# DC309A_RXIN.net
KiCad netlist of a schematic drawn in Altium Designer
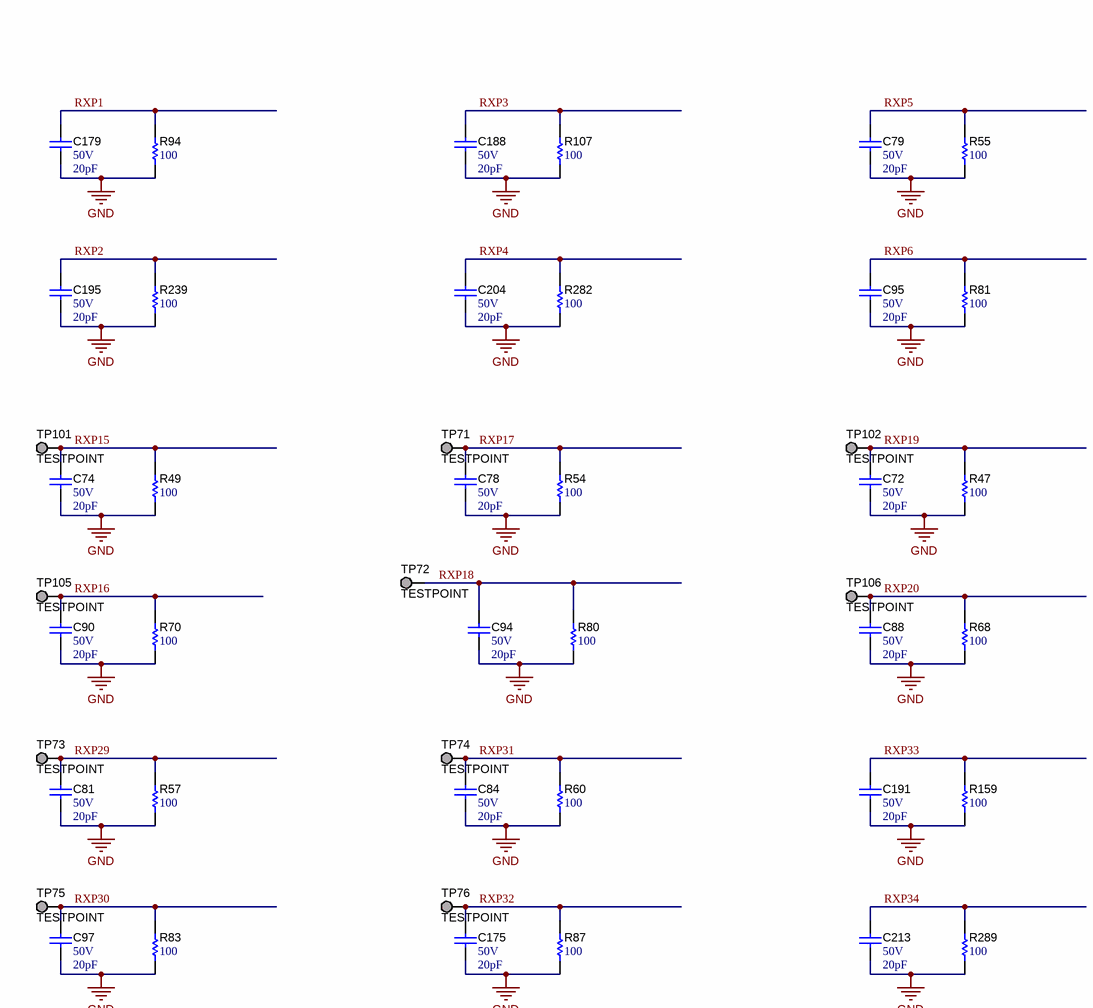
[diagram p0: DC309A_RXIN.SchDoc, top left]
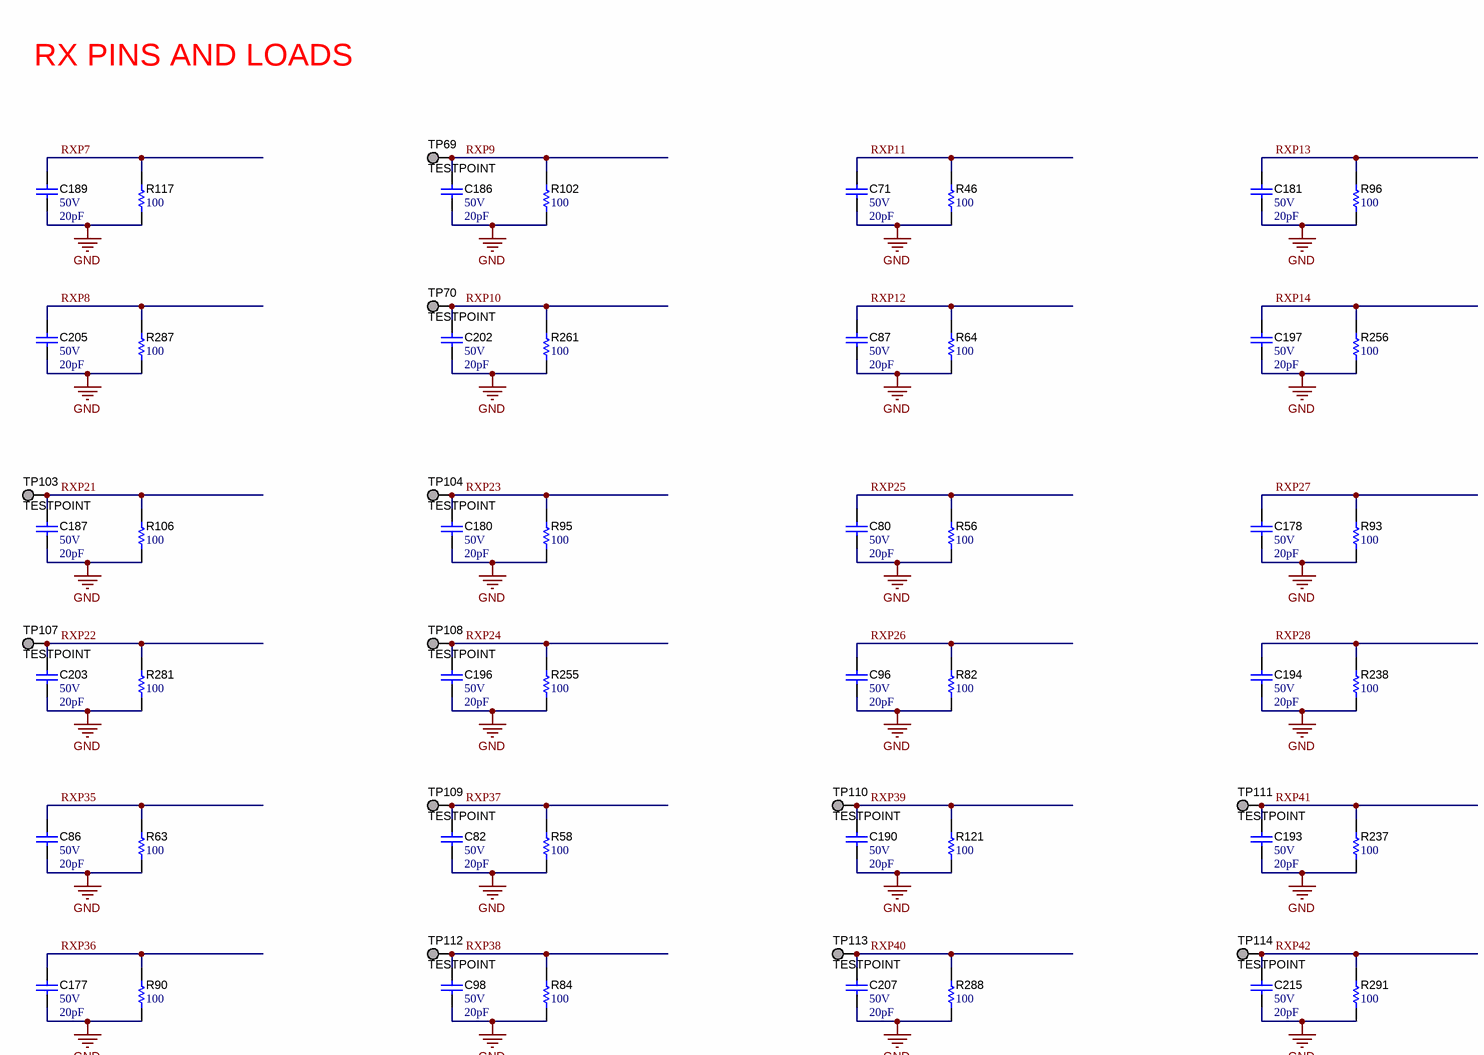
[diagram p1: DC309A_RXIN.SchDoc, top right]
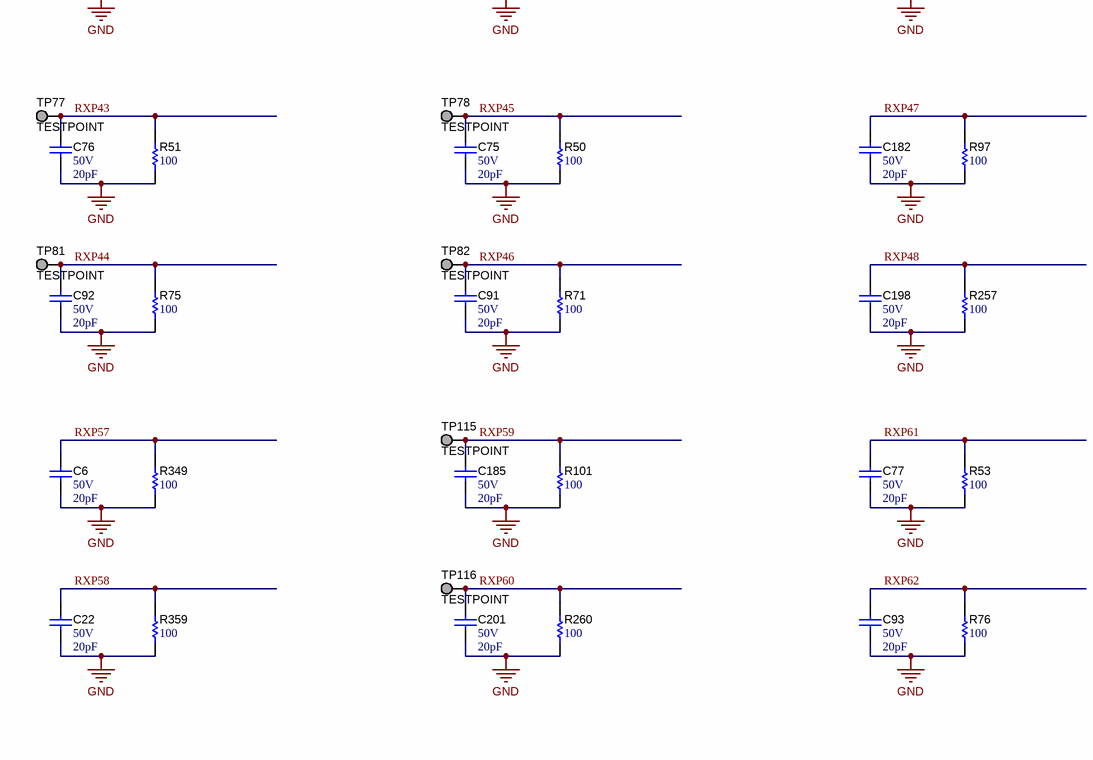
[diagram p2: DC309A_RXIN.SchDoc, bottom left]
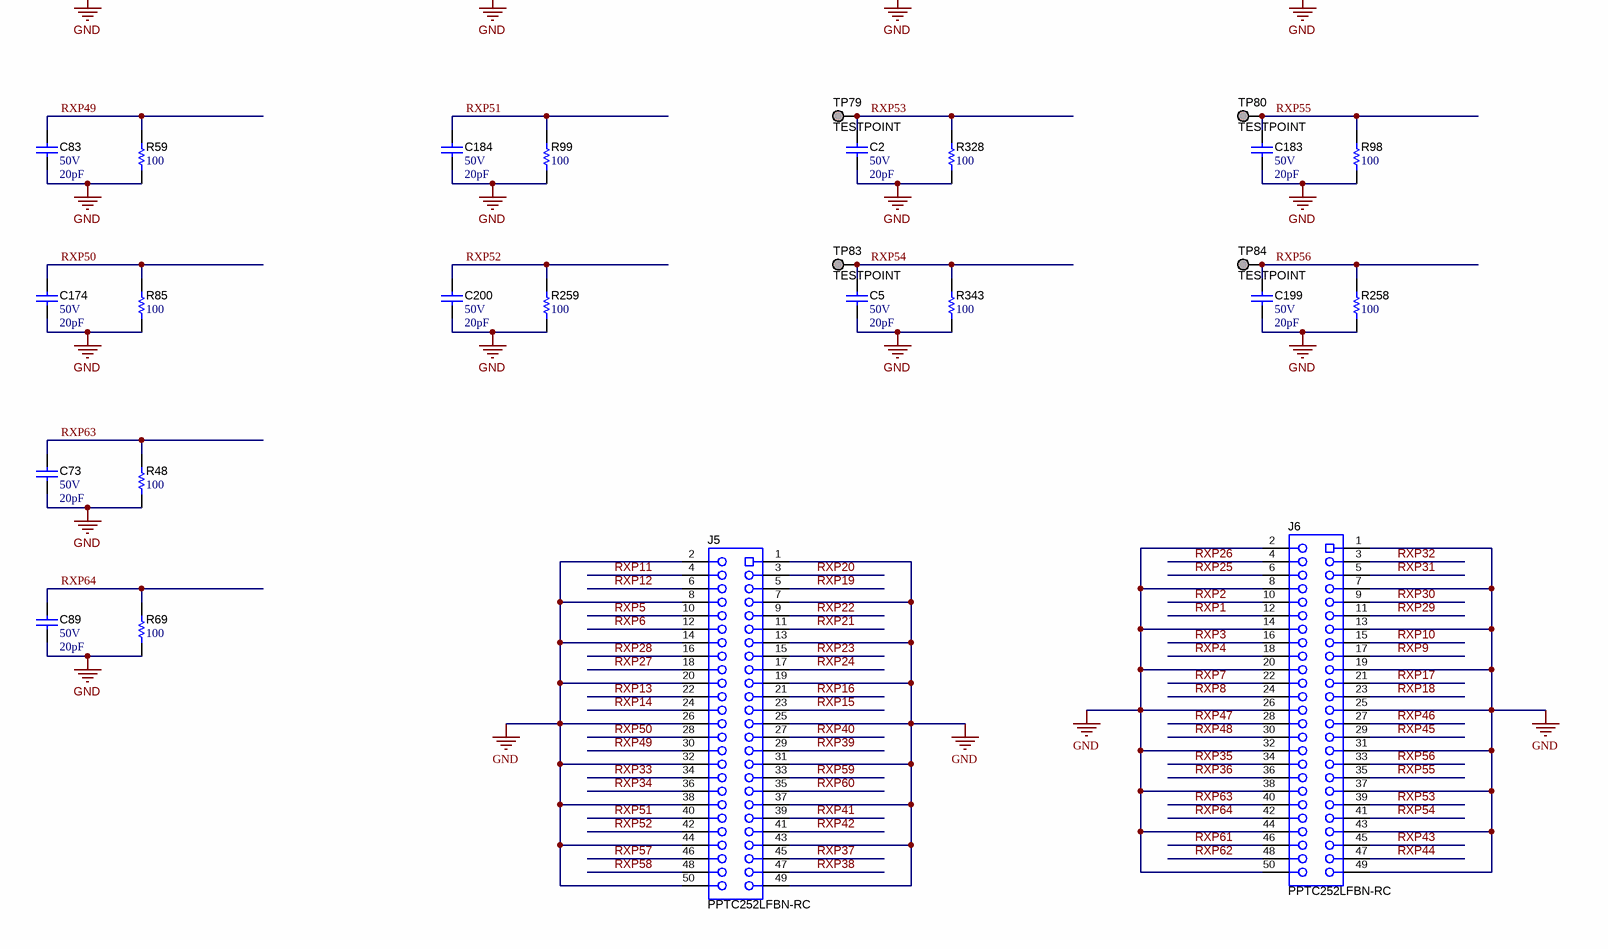
[diagram p3: DC309A_RXIN.SchDoc, bottom right]

(export (version "E")
  (design (tool "Eeschema 10.0.6"))
  (components
    (comp (ref "C2")
      (value "C0402C200J5GACTU")
      (footprint "0402")
      (description "CAP, CERM, 20 pF, 50 V, +/- 5%, C0G/NP0, 0402")
      (fields
        (field (name "MANUFACTURER") "Kemet")
        (field (name "VDC_V") "50V")
        (field (name "VALUEDISPLAYED") "20pF")
        (field (name "PUBLISHER") "Texas Instruments")
      )
      (libsource (lib "Altium Vault - TI") (part "Capacitor"))
    )
    (comp (ref "C5")
      (value "C0402C200J5GACTU")
      (footprint "0402")
      (description "CAP, CERM, 20 pF, 50 V, +/- 5%, C0G/NP0, 0402")
      (fields
        (field (name "MANUFACTURER") "Kemet")
        (field (name "VDC_V") "50V")
        (field (name "VALUEDISPLAYED") "20pF")
        (field (name "PUBLISHER") "Texas Instruments")
      )
      (libsource (lib "Altium Vault - TI") (part "Capacitor"))
    )
    (comp (ref "C6")
      (value "C0402C200J5GACTU")
      (footprint "0402")
      (description "CAP, CERM, 20 pF, 50 V, +/- 5%, C0G/NP0, 0402")
      (fields
        (field (name "MANUFACTURER") "Kemet")
        (field (name "VDC_V") "50V")
        (field (name "VALUEDISPLAYED") "20pF")
        (field (name "PUBLISHER") "Texas Instruments")
      )
      (libsource (lib "Altium Vault - TI") (part "Capacitor"))
    )
    (comp (ref "C22")
      (value "C0402C200J5GACTU")
      (footprint "0402")
      (description "CAP, CERM, 20 pF, 50 V, +/- 5%, C0G/NP0, 0402")
      (fields
        (field (name "MANUFACTURER") "Kemet")
        (field (name "VDC_V") "50V")
        (field (name "VALUEDISPLAYED") "20pF")
        (field (name "PUBLISHER") "Texas Instruments")
      )
      (libsource (lib "Altium Vault - TI") (part "Capacitor"))
    )
    (comp (ref "C71")
      (value "C0402C200J5GACTU")
      (footprint "0402")
      (description "CAP, CERM, 20 pF, 50 V, +/- 5%, C0G/NP0, 0402")
      (fields
        (field (name "MANUFACTURER") "Kemet")
        (field (name "VDC_V") "50V")
        (field (name "VALUEDISPLAYED") "20pF")
        (field (name "PUBLISHER") "Texas Instruments")
      )
      (libsource (lib "Altium Vault - TI") (part "Capacitor"))
    )
    (comp (ref "C72")
      (value "C0402C200J5GACTU")
      (footprint "0402")
      (description "CAP, CERM, 20 pF, 50 V, +/- 5%, C0G/NP0, 0402")
      (fields
        (field (name "MANUFACTURER") "Kemet")
        (field (name "VDC_V") "50V")
        (field (name "VALUEDISPLAYED") "20pF")
        (field (name "PUBLISHER") "Texas Instruments")
      )
      (libsource (lib "Altium Vault - TI") (part "Capacitor"))
    )
    (comp (ref "C73")
      (value "C0402C200J5GACTU")
      (footprint "0402")
      (description "CAP, CERM, 20 pF, 50 V, +/- 5%, C0G/NP0, 0402")
      (fields
        (field (name "MANUFACTURER") "Kemet")
        (field (name "VDC_V") "50V")
        (field (name "VALUEDISPLAYED") "20pF")
        (field (name "PUBLISHER") "Texas Instruments")
      )
      (libsource (lib "Altium Vault - TI") (part "Capacitor"))
    )
    (comp (ref "C74")
      (value "C0402C200J5GACTU")
      (footprint "0402")
      (description "CAP, CERM, 20 pF, 50 V, +/- 5%, C0G/NP0, 0402")
      (fields
        (field (name "MANUFACTURER") "Kemet")
        (field (name "VDC_V") "50V")
        (field (name "VALUEDISPLAYED") "20pF")
        (field (name "PUBLISHER") "Texas Instruments")
      )
      (libsource (lib "Altium Vault - TI") (part "Capacitor"))
    )
    (comp (ref "C75")
      (value "C0402C200J5GACTU")
      (footprint "0402")
      (description "CAP, CERM, 20 pF, 50 V, +/- 5%, C0G/NP0, 0402")
      (fields
        (field (name "MANUFACTURER") "Kemet")
        (field (name "VDC_V") "50V")
        (field (name "VALUEDISPLAYED") "20pF")
        (field (name "PUBLISHER") "Texas Instruments")
      )
      (libsource (lib "Altium Vault - TI") (part "Capacitor"))
    )
    (comp (ref "C76")
      (value "C0402C200J5GACTU")
      (footprint "0402")
      (description "CAP, CERM, 20 pF, 50 V, +/- 5%, C0G/NP0, 0402")
      (fields
        (field (name "MANUFACTURER") "Kemet")
        (field (name "VDC_V") "50V")
        (field (name "VALUEDISPLAYED") "20pF")
        (field (name "PUBLISHER") "Texas Instruments")
      )
      (libsource (lib "Altium Vault - TI") (part "Capacitor"))
    )
    (comp (ref "C77")
      (value "C0402C200J5GACTU")
      (footprint "0402")
      (description "CAP, CERM, 20 pF, 50 V, +/- 5%, C0G/NP0, 0402")
      (fields
        (field (name "MANUFACTURER") "Kemet")
        (field (name "VDC_V") "50V")
        (field (name "VALUEDISPLAYED") "20pF")
        (field (name "PUBLISHER") "Texas Instruments")
      )
      (libsource (lib "Altium Vault - TI") (part "Capacitor"))
    )
    (comp (ref "C78")
      (value "C0402C200J5GACTU")
      (footprint "0402")
      (description "CAP, CERM, 20 pF, 50 V, +/- 5%, C0G/NP0, 0402")
      (fields
        (field (name "MANUFACTURER") "Kemet")
        (field (name "VDC_V") "50V")
        (field (name "VALUEDISPLAYED") "20pF")
        (field (name "PUBLISHER") "Texas Instruments")
      )
      (libsource (lib "Altium Vault - TI") (part "Capacitor"))
    )
    (comp (ref "C79")
      (value "C0402C200J5GACTU")
      (footprint "0402")
      (description "CAP, CERM, 20 pF, 50 V, +/- 5%, C0G/NP0, 0402")
      (fields
        (field (name "MANUFACTURER") "Kemet")
        (field (name "VDC_V") "50V")
        (field (name "VALUEDISPLAYED") "20pF")
        (field (name "PUBLISHER") "Texas Instruments")
      )
      (libsource (lib "Altium Vault - TI") (part "Capacitor"))
    )
    (comp (ref "C80")
      (value "C0402C200J5GACTU")
      (footprint "0402")
      (description "CAP, CERM, 20 pF, 50 V, +/- 5%, C0G/NP0, 0402")
      (fields
        (field (name "MANUFACTURER") "Kemet")
        (field (name "VDC_V") "50V")
        (field (name "VALUEDISPLAYED") "20pF")
        (field (name "PUBLISHER") "Texas Instruments")
      )
      (libsource (lib "Altium Vault - TI") (part "Capacitor"))
    )
    (comp (ref "C81")
      (value "C0402C200J5GACTU")
      (footprint "0402")
      (description "CAP, CERM, 20 pF, 50 V, +/- 5%, C0G/NP0, 0402")
      (fields
        (field (name "MANUFACTURER") "Kemet")
        (field (name "VDC_V") "50V")
        (field (name "VALUEDISPLAYED") "20pF")
        (field (name "PUBLISHER") "Texas Instruments")
      )
      (libsource (lib "Altium Vault - TI") (part "Capacitor"))
    )
    (comp (ref "C82")
      (value "C0402C200J5GACTU")
      (footprint "0402")
      (description "CAP, CERM, 20 pF, 50 V, +/- 5%, C0G/NP0, 0402")
      (fields
        (field (name "MANUFACTURER") "Kemet")
        (field (name "VDC_V") "50V")
        (field (name "VALUEDISPLAYED") "20pF")
        (field (name "PUBLISHER") "Texas Instruments")
      )
      (libsource (lib "Altium Vault - TI") (part "Capacitor"))
    )
    (comp (ref "C83")
      (value "C0402C200J5GACTU")
      (footprint "0402")
      (description "CAP, CERM, 20 pF, 50 V, +/- 5%, C0G/NP0, 0402")
      (fields
        (field (name "MANUFACTURER") "Kemet")
        (field (name "VDC_V") "50V")
        (field (name "VALUEDISPLAYED") "20pF")
        (field (name "PUBLISHER") "Texas Instruments")
      )
      (libsource (lib "Altium Vault - TI") (part "Capacitor"))
    )
    (comp (ref "C84")
      (value "C0402C200J5GACTU")
      (footprint "0402")
      (description "CAP, CERM, 20 pF, 50 V, +/- 5%, C0G/NP0, 0402")
      (fields
        (field (name "MANUFACTURER") "Kemet")
        (field (name "VDC_V") "50V")
        (field (name "VALUEDISPLAYED") "20pF")
        (field (name "PUBLISHER") "Texas Instruments")
      )
      (libsource (lib "Altium Vault - TI") (part "Capacitor"))
    )
    (comp (ref "C86")
      (value "C0402C200J5GACTU")
      (footprint "0402")
      (description "CAP, CERM, 20 pF, 50 V, +/- 5%, C0G/NP0, 0402")
      (fields
        (field (name "MANUFACTURER") "Kemet")
        (field (name "VDC_V") "50V")
        (field (name "VALUEDISPLAYED") "20pF")
        (field (name "PUBLISHER") "Texas Instruments")
      )
      (libsource (lib "Altium Vault - TI") (part "Capacitor"))
    )
    (comp (ref "C87")
      (value "C0402C200J5GACTU")
      (footprint "0402")
      (description "CAP, CERM, 20 pF, 50 V, +/- 5%, C0G/NP0, 0402")
      (fields
        (field (name "MANUFACTURER") "Kemet")
        (field (name "VDC_V") "50V")
        (field (name "VALUEDISPLAYED") "20pF")
        (field (name "PUBLISHER") "Texas Instruments")
      )
      (libsource (lib "Altium Vault - TI") (part "Capacitor"))
    )
    (comp (ref "C88")
      (value "C0402C200J5GACTU")
      (footprint "0402")
      (description "CAP, CERM, 20 pF, 50 V, +/- 5%, C0G/NP0, 0402")
      (fields
        (field (name "MANUFACTURER") "Kemet")
        (field (name "VDC_V") "50V")
        (field (name "VALUEDISPLAYED") "20pF")
        (field (name "PUBLISHER") "Texas Instruments")
      )
      (libsource (lib "Altium Vault - TI") (part "Capacitor"))
    )
    (comp (ref "C89")
      (value "C0402C200J5GACTU")
      (footprint "0402")
      (description "CAP, CERM, 20 pF, 50 V, +/- 5%, C0G/NP0, 0402")
      (fields
        (field (name "MANUFACTURER") "Kemet")
        (field (name "VDC_V") "50V")
        (field (name "VALUEDISPLAYED") "20pF")
        (field (name "PUBLISHER") "Texas Instruments")
      )
      (libsource (lib "Altium Vault - TI") (part "Capacitor"))
    )
    (comp (ref "C90")
      (value "C0402C200J5GACTU")
      (footprint "0402")
      (description "CAP, CERM, 20 pF, 50 V, +/- 5%, C0G/NP0, 0402")
      (fields
        (field (name "MANUFACTURER") "Kemet")
        (field (name "VDC_V") "50V")
        (field (name "VALUEDISPLAYED") "20pF")
        (field (name "PUBLISHER") "Texas Instruments")
      )
      (libsource (lib "Altium Vault - TI") (part "Capacitor"))
    )
    (comp (ref "C91")
      (value "C0402C200J5GACTU")
      (footprint "0402")
      (description "CAP, CERM, 20 pF, 50 V, +/- 5%, C0G/NP0, 0402")
      (fields
        (field (name "MANUFACTURER") "Kemet")
        (field (name "VDC_V") "50V")
        (field (name "VALUEDISPLAYED") "20pF")
        (field (name "PUBLISHER") "Texas Instruments")
      )
      (libsource (lib "Altium Vault - TI") (part "Capacitor"))
    )
    (comp (ref "C92")
      (value "C0402C200J5GACTU")
      (footprint "0402")
      (description "CAP, CERM, 20 pF, 50 V, +/- 5%, C0G/NP0, 0402")
      (fields
        (field (name "MANUFACTURER") "Kemet")
        (field (name "VDC_V") "50V")
        (field (name "VALUEDISPLAYED") "20pF")
        (field (name "PUBLISHER") "Texas Instruments")
      )
      (libsource (lib "Altium Vault - TI") (part "Capacitor"))
    )
    (comp (ref "C93")
      (value "C0402C200J5GACTU")
      (footprint "0402")
      (description "CAP, CERM, 20 pF, 50 V, +/- 5%, C0G/NP0, 0402")
      (fields
        (field (name "MANUFACTURER") "Kemet")
        (field (name "VDC_V") "50V")
        (field (name "VALUEDISPLAYED") "20pF")
        (field (name "PUBLISHER") "Texas Instruments")
      )
      (libsource (lib "Altium Vault - TI") (part "Capacitor"))
    )
    (comp (ref "C94")
      (value "C0402C200J5GACTU")
      (footprint "0402")
      (description "CAP, CERM, 20 pF, 50 V, +/- 5%, C0G/NP0, 0402")
      (fields
        (field (name "MANUFACTURER") "Kemet")
        (field (name "VDC_V") "50V")
        (field (name "VALUEDISPLAYED") "20pF")
        (field (name "PUBLISHER") "Texas Instruments")
      )
      (libsource (lib "Altium Vault - TI") (part "Capacitor"))
    )
    (comp (ref "C95")
      (value "C0402C200J5GACTU")
      (footprint "0402")
      (description "CAP, CERM, 20 pF, 50 V, +/- 5%, C0G/NP0, 0402")
      (fields
        (field (name "MANUFACTURER") "Kemet")
        (field (name "VDC_V") "50V")
        (field (name "VALUEDISPLAYED") "20pF")
        (field (name "PUBLISHER") "Texas Instruments")
      )
      (libsource (lib "Altium Vault - TI") (part "Capacitor"))
    )
    (comp (ref "C96")
      (value "C0402C200J5GACTU")
      (footprint "0402")
      (description "CAP, CERM, 20 pF, 50 V, +/- 5%, C0G/NP0, 0402")
      (fields
        (field (name "MANUFACTURER") "Kemet")
        (field (name "VDC_V") "50V")
        (field (name "VALUEDISPLAYED") "20pF")
        (field (name "PUBLISHER") "Texas Instruments")
      )
      (libsource (lib "Altium Vault - TI") (part "Capacitor"))
    )
    (comp (ref "C97")
      (value "C0402C200J5GACTU")
      (footprint "0402")
      (description "CAP, CERM, 20 pF, 50 V, +/- 5%, C0G/NP0, 0402")
      (fields
        (field (name "MANUFACTURER") "Kemet")
        (field (name "VDC_V") "50V")
        (field (name "VALUEDISPLAYED") "20pF")
        (field (name "PUBLISHER") "Texas Instruments")
      )
      (libsource (lib "Altium Vault - TI") (part "Capacitor"))
    )
    (comp (ref "C98")
      (value "C0402C200J5GACTU")
      (footprint "0402")
      (description "CAP, CERM, 20 pF, 50 V, +/- 5%, C0G/NP0, 0402")
      (fields
        (field (name "MANUFACTURER") "Kemet")
        (field (name "VDC_V") "50V")
        (field (name "VALUEDISPLAYED") "20pF")
        (field (name "PUBLISHER") "Texas Instruments")
      )
      (libsource (lib "Altium Vault - TI") (part "Capacitor"))
    )
    (comp (ref "C174")
      (value "C0402C200J5GACTU")
      (footprint "0402")
      (description "CAP, CERM, 20 pF, 50 V, +/- 5%, C0G/NP0, 0402")
      (fields
        (field (name "MANUFACTURER") "Kemet")
        (field (name "VDC_V") "50V")
        (field (name "VALUEDISPLAYED") "20pF")
        (field (name "PUBLISHER") "Texas Instruments")
      )
      (libsource (lib "Altium Vault - TI") (part "Capacitor"))
    )
    (comp (ref "C175")
      (value "C0402C200J5GACTU")
      (footprint "0402")
      (description "CAP, CERM, 20 pF, 50 V, +/- 5%, C0G/NP0, 0402")
      (fields
        (field (name "MANUFACTURER") "Kemet")
        (field (name "VDC_V") "50V")
        (field (name "VALUEDISPLAYED") "20pF")
        (field (name "PUBLISHER") "Texas Instruments")
      )
      (libsource (lib "Altium Vault - TI") (part "Capacitor"))
    )
    (comp (ref "C177")
      (value "C0402C200J5GACTU")
      (footprint "0402")
      (description "CAP, CERM, 20 pF, 50 V, +/- 5%, C0G/NP0, 0402")
      (fields
        (field (name "MANUFACTURER") "Kemet")
        (field (name "VDC_V") "50V")
        (field (name "VALUEDISPLAYED") "20pF")
        (field (name "PUBLISHER") "Texas Instruments")
      )
      (libsource (lib "Altium Vault - TI") (part "Capacitor"))
    )
    (comp (ref "C178")
      (value "C0402C200J5GACTU")
      (footprint "0402")
      (description "CAP, CERM, 20 pF, 50 V, +/- 5%, C0G/NP0, 0402")
      (fields
        (field (name "MANUFACTURER") "Kemet")
        (field (name "VDC_V") "50V")
        (field (name "VALUEDISPLAYED") "20pF")
        (field (name "PUBLISHER") "Texas Instruments")
      )
      (libsource (lib "Altium Vault - TI") (part "Capacitor"))
    )
    (comp (ref "C179")
      (value "C0402C200J5GACTU")
      (footprint "0402")
      (description "CAP, CERM, 20 pF, 50 V, +/- 5%, C0G/NP0, 0402")
      (fields
        (field (name "MANUFACTURER") "Kemet")
        (field (name "VDC_V") "50V")
        (field (name "VALUEDISPLAYED") "20pF")
        (field (name "PUBLISHER") "Texas Instruments")
      )
      (libsource (lib "Altium Vault - TI") (part "Capacitor"))
    )
    (comp (ref "C180")
      (value "C0402C200J5GACTU")
      (footprint "0402")
      (description "CAP, CERM, 20 pF, 50 V, +/- 5%, C0G/NP0, 0402")
      (fields
        (field (name "MANUFACTURER") "Kemet")
        (field (name "VDC_V") "50V")
        (field (name "VALUEDISPLAYED") "20pF")
        (field (name "PUBLISHER") "Texas Instruments")
      )
      (libsource (lib "Altium Vault - TI") (part "Capacitor"))
    )
    (comp (ref "C181")
      (value "C0402C200J5GACTU")
      (footprint "0402")
      (description "CAP, CERM, 20 pF, 50 V, +/- 5%, C0G/NP0, 0402")
      (fields
        (field (name "MANUFACTURER") "Kemet")
        (field (name "VDC_V") "50V")
        (field (name "VALUEDISPLAYED") "20pF")
        (field (name "PUBLISHER") "Texas Instruments")
      )
      (libsource (lib "Altium Vault - TI") (part "Capacitor"))
    )
    (comp (ref "C182")
      (value "C0402C200J5GACTU")
      (footprint "0402")
      (description "CAP, CERM, 20 pF, 50 V, +/- 5%, C0G/NP0, 0402")
      (fields
        (field (name "MANUFACTURER") "Kemet")
        (field (name "VDC_V") "50V")
        (field (name "VALUEDISPLAYED") "20pF")
        (field (name "PUBLISHER") "Texas Instruments")
      )
      (libsource (lib "Altium Vault - TI") (part "Capacitor"))
    )
    (comp (ref "C183")
      (value "C0402C200J5GACTU")
      (footprint "0402")
      (description "CAP, CERM, 20 pF, 50 V, +/- 5%, C0G/NP0, 0402")
      (fields
        (field (name "MANUFACTURER") "Kemet")
        (field (name "VDC_V") "50V")
        (field (name "VALUEDISPLAYED") "20pF")
        (field (name "PUBLISHER") "Texas Instruments")
      )
      (libsource (lib "Altium Vault - TI") (part "Capacitor"))
    )
    (comp (ref "C184")
      (value "C0402C200J5GACTU")
      (footprint "0402")
      (description "CAP, CERM, 20 pF, 50 V, +/- 5%, C0G/NP0, 0402")
      (fields
        (field (name "MANUFACTURER") "Kemet")
        (field (name "VDC_V") "50V")
        (field (name "VALUEDISPLAYED") "20pF")
        (field (name "PUBLISHER") "Texas Instruments")
      )
      (libsource (lib "Altium Vault - TI") (part "Capacitor"))
    )
    (comp (ref "C185")
      (value "C0402C200J5GACTU")
      (footprint "0402")
      (description "CAP, CERM, 20 pF, 50 V, +/- 5%, C0G/NP0, 0402")
      (fields
        (field (name "MANUFACTURER") "Kemet")
        (field (name "VDC_V") "50V")
        (field (name "VALUEDISPLAYED") "20pF")
        (field (name "PUBLISHER") "Texas Instruments")
      )
      (libsource (lib "Altium Vault - TI") (part "Capacitor"))
    )
    (comp (ref "C186")
      (value "C0402C200J5GACTU")
      (footprint "0402")
      (description "CAP, CERM, 20 pF, 50 V, +/- 5%, C0G/NP0, 0402")
      (fields
        (field (name "MANUFACTURER") "Kemet")
        (field (name "VDC_V") "50V")
        (field (name "VALUEDISPLAYED") "20pF")
        (field (name "PUBLISHER") "Texas Instruments")
      )
      (libsource (lib "Altium Vault - TI") (part "Capacitor"))
    )
    (comp (ref "C187")
      (value "C0402C200J5GACTU")
      (footprint "0402")
      (description "CAP, CERM, 20 pF, 50 V, +/- 5%, C0G/NP0, 0402")
      (fields
        (field (name "MANUFACTURER") "Kemet")
        (field (name "VDC_V") "50V")
        (field (name "VALUEDISPLAYED") "20pF")
        (field (name "PUBLISHER") "Texas Instruments")
      )
      (libsource (lib "Altium Vault - TI") (part "Capacitor"))
    )
    (comp (ref "C188")
      (value "C0402C200J5GACTU")
      (footprint "0402")
      (description "CAP, CERM, 20 pF, 50 V, +/- 5%, C0G/NP0, 0402")
      (fields
        (field (name "MANUFACTURER") "Kemet")
        (field (name "VDC_V") "50V")
        (field (name "VALUEDISPLAYED") "20pF")
        (field (name "PUBLISHER") "Texas Instruments")
      )
      (libsource (lib "Altium Vault - TI") (part "Capacitor"))
    )
    (comp (ref "C189")
      (value "C0402C200J5GACTU")
      (footprint "0402")
      (description "CAP, CERM, 20 pF, 50 V, +/- 5%, C0G/NP0, 0402")
      (fields
        (field (name "MANUFACTURER") "Kemet")
        (field (name "VDC_V") "50V")
        (field (name "VALUEDISPLAYED") "20pF")
        (field (name "PUBLISHER") "Texas Instruments")
      )
      (libsource (lib "Altium Vault - TI") (part "Capacitor"))
    )
    (comp (ref "C190")
      (value "C0402C200J5GACTU")
      (footprint "0402")
      (description "CAP, CERM, 20 pF, 50 V, +/- 5%, C0G/NP0, 0402")
      (fields
        (field (name "MANUFACTURER") "Kemet")
        (field (name "VDC_V") "50V")
        (field (name "VALUEDISPLAYED") "20pF")
        (field (name "PUBLISHER") "Texas Instruments")
      )
      (libsource (lib "Altium Vault - TI") (part "Capacitor"))
    )
    (comp (ref "C191")
      (value "C0402C200J5GACTU")
      (footprint "0402")
      (description "CAP, CERM, 20 pF, 50 V, +/- 5%, C0G/NP0, 0402")
      (fields
        (field (name "MANUFACTURER") "Kemet")
        (field (name "VDC_V") "50V")
        (field (name "VALUEDISPLAYED") "20pF")
        (field (name "PUBLISHER") "Texas Instruments")
      )
      (libsource (lib "Altium Vault - TI") (part "Capacitor"))
    )
    (comp (ref "C193")
      (value "C0402C200J5GACTU")
      (footprint "0402")
      (description "CAP, CERM, 20 pF, 50 V, +/- 5%, C0G/NP0, 0402")
      (fields
        (field (name "MANUFACTURER") "Kemet")
        (field (name "VDC_V") "50V")
        (field (name "VALUEDISPLAYED") "20pF")
        (field (name "PUBLISHER") "Texas Instruments")
      )
      (libsource (lib "Altium Vault - TI") (part "Capacitor"))
    )
    (comp (ref "C194")
      (value "C0402C200J5GACTU")
      (footprint "0402")
      (description "CAP, CERM, 20 pF, 50 V, +/- 5%, C0G/NP0, 0402")
      (fields
        (field (name "MANUFACTURER") "Kemet")
        (field (name "VDC_V") "50V")
        (field (name "VALUEDISPLAYED") "20pF")
        (field (name "PUBLISHER") "Texas Instruments")
      )
      (libsource (lib "Altium Vault - TI") (part "Capacitor"))
    )
    (comp (ref "C195")
      (value "C0402C200J5GACTU")
      (footprint "0402")
      (description "CAP, CERM, 20 pF, 50 V, +/- 5%, C0G/NP0, 0402")
      (fields
        (field (name "MANUFACTURER") "Kemet")
        (field (name "VDC_V") "50V")
        (field (name "VALUEDISPLAYED") "20pF")
        (field (name "PUBLISHER") "Texas Instruments")
      )
      (libsource (lib "Altium Vault - TI") (part "Capacitor"))
    )
    (comp (ref "C196")
      (value "C0402C200J5GACTU")
      (footprint "0402")
      (description "CAP, CERM, 20 pF, 50 V, +/- 5%, C0G/NP0, 0402")
      (fields
        (field (name "MANUFACTURER") "Kemet")
        (field (name "VDC_V") "50V")
        (field (name "VALUEDISPLAYED") "20pF")
        (field (name "PUBLISHER") "Texas Instruments")
      )
      (libsource (lib "Altium Vault - TI") (part "Capacitor"))
    )
    (comp (ref "C197")
      (value "C0402C200J5GACTU")
      (footprint "0402")
      (description "CAP, CERM, 20 pF, 50 V, +/- 5%, C0G/NP0, 0402")
      (fields
        (field (name "MANUFACTURER") "Kemet")
        (field (name "VDC_V") "50V")
        (field (name "VALUEDISPLAYED") "20pF")
        (field (name "PUBLISHER") "Texas Instruments")
      )
      (libsource (lib "Altium Vault - TI") (part "Capacitor"))
    )
    (comp (ref "C198")
      (value "C0402C200J5GACTU")
      (footprint "0402")
      (description "CAP, CERM, 20 pF, 50 V, +/- 5%, C0G/NP0, 0402")
      (fields
        (field (name "MANUFACTURER") "Kemet")
        (field (name "VDC_V") "50V")
        (field (name "VALUEDISPLAYED") "20pF")
        (field (name "PUBLISHER") "Texas Instruments")
      )
      (libsource (lib "Altium Vault - TI") (part "Capacitor"))
    )
    (comp (ref "C199")
      (value "C0402C200J5GACTU")
      (footprint "0402")
      (description "CAP, CERM, 20 pF, 50 V, +/- 5%, C0G/NP0, 0402")
      (fields
        (field (name "MANUFACTURER") "Kemet")
        (field (name "VDC_V") "50V")
        (field (name "VALUEDISPLAYED") "20pF")
        (field (name "PUBLISHER") "Texas Instruments")
      )
      (libsource (lib "Altium Vault - TI") (part "Capacitor"))
    )
    (comp (ref "C200")
      (value "C0402C200J5GACTU")
      (footprint "0402")
      (description "CAP, CERM, 20 pF, 50 V, +/- 5%, C0G/NP0, 0402")
      (fields
        (field (name "MANUFACTURER") "Kemet")
        (field (name "VDC_V") "50V")
        (field (name "VALUEDISPLAYED") "20pF")
        (field (name "PUBLISHER") "Texas Instruments")
      )
      (libsource (lib "Altium Vault - TI") (part "Capacitor"))
    )
    (comp (ref "C201")
      (value "C0402C200J5GACTU")
      (footprint "0402")
      (description "CAP, CERM, 20 pF, 50 V, +/- 5%, C0G/NP0, 0402")
      (fields
        (field (name "MANUFACTURER") "Kemet")
        (field (name "VDC_V") "50V")
        (field (name "VALUEDISPLAYED") "20pF")
        (field (name "PUBLISHER") "Texas Instruments")
      )
      (libsource (lib "Altium Vault - TI") (part "Capacitor"))
    )
    (comp (ref "C202")
      (value "C0402C200J5GACTU")
      (footprint "0402")
      (description "CAP, CERM, 20 pF, 50 V, +/- 5%, C0G/NP0, 0402")
      (fields
        (field (name "MANUFACTURER") "Kemet")
        (field (name "VDC_V") "50V")
        (field (name "VALUEDISPLAYED") "20pF")
        (field (name "PUBLISHER") "Texas Instruments")
      )
      (libsource (lib "Altium Vault - TI") (part "Capacitor"))
    )
    (comp (ref "C203")
      (value "C0402C200J5GACTU")
      (footprint "0402")
      (description "CAP, CERM, 20 pF, 50 V, +/- 5%, C0G/NP0, 0402")
      (fields
        (field (name "MANUFACTURER") "Kemet")
        (field (name "VDC_V") "50V")
        (field (name "VALUEDISPLAYED") "20pF")
        (field (name "PUBLISHER") "Texas Instruments")
      )
      (libsource (lib "Altium Vault - TI") (part "Capacitor"))
    )
    (comp (ref "C204")
      (value "C0402C200J5GACTU")
      (footprint "0402")
      (description "CAP, CERM, 20 pF, 50 V, +/- 5%, C0G/NP0, 0402")
      (fields
        (field (name "MANUFACTURER") "Kemet")
        (field (name "VDC_V") "50V")
        (field (name "VALUEDISPLAYED") "20pF")
        (field (name "PUBLISHER") "Texas Instruments")
      )
      (libsource (lib "Altium Vault - TI") (part "Capacitor"))
    )
    (comp (ref "C205")
      (value "C0402C200J5GACTU")
      (footprint "0402")
      (description "CAP, CERM, 20 pF, 50 V, +/- 5%, C0G/NP0, 0402")
      (fields
        (field (name "MANUFACTURER") "Kemet")
        (field (name "VDC_V") "50V")
        (field (name "VALUEDISPLAYED") "20pF")
        (field (name "PUBLISHER") "Texas Instruments")
      )
      (libsource (lib "Altium Vault - TI") (part "Capacitor"))
    )
    (comp (ref "C207")
      (value "C0402C200J5GACTU")
      (footprint "0402")
      (description "CAP, CERM, 20 pF, 50 V, +/- 5%, C0G/NP0, 0402")
      (fields
        (field (name "MANUFACTURER") "Kemet")
        (field (name "VDC_V") "50V")
        (field (name "VALUEDISPLAYED") "20pF")
        (field (name "PUBLISHER") "Texas Instruments")
      )
      (libsource (lib "Altium Vault - TI") (part "Capacitor"))
    )
    (comp (ref "C213")
      (value "C0402C200J5GACTU")
      (footprint "0402")
      (description "CAP, CERM, 20 pF, 50 V, +/- 5%, C0G/NP0, 0402")
      (fields
        (field (name "MANUFACTURER") "Kemet")
        (field (name "VDC_V") "50V")
        (field (name "VALUEDISPLAYED") "20pF")
        (field (name "PUBLISHER") "Texas Instruments")
      )
      (libsource (lib "Altium Vault - TI") (part "Capacitor"))
    )
    (comp (ref "C215")
      (value "C0402C200J5GACTU")
      (footprint "0402")
      (description "CAP, CERM, 20 pF, 50 V, +/- 5%, C0G/NP0, 0402")
      (fields
        (field (name "MANUFACTURER") "Kemet")
        (field (name "VDC_V") "50V")
        (field (name "VALUEDISPLAYED") "20pF")
        (field (name "PUBLISHER") "Texas Instruments")
      )
      (libsource (lib "Altium Vault - TI") (part "Capacitor"))
    )
    (comp (ref "J5")
      (value "PPTC252LFBN-RC")
      (footprint "Sullins_xPxC252LFBN")
      (description "Receptacle, 2.54mm, 25x2, Tin, TH")
      (fields
        (field (name "MANUFACTURER") "Sullins Connector Solutions")
        (field (name "PUBLISHER") "Texas Instruments")
      )
      (libsource (lib "Altium Vault - TI") (part "Receptacle_25x2"))
    )
    (comp (ref "J6")
      (value "PPTC252LFBN-RC")
      (footprint "Sullins_xPxC252LFBN")
      (description "Receptacle, 2.54mm, 25x2, Tin, TH")
      (fields
        (field (name "MANUFACTURER") "Sullins Connector Solutions")
        (field (name "PUBLISHER") "Texas Instruments")
      )
      (libsource (lib "Altium Vault - TI") (part "Receptacle_25x2"))
    )
    (comp (ref "R46")
      (value "RG1005P-101-B-T5")
      (footprint "0402")
      (description "RES, 100, 0.1%, 0.063 W, 0402")
      (fields
        (field (name "MANUFACTURER") "Susumu Co Ltd")
        (field (name "VALUEDISPLAYED") "100")
        (field (name "PUBLISHER") "Texas Instruments")
      )
      (libsource (lib "Altium Vault - TI") (part "Resistor"))
    )
    (comp (ref "R47")
      (value "RG1005P-101-B-T5")
      (footprint "0402")
      (description "RES, 100, 0.1%, 0.063 W, 0402")
      (fields
        (field (name "MANUFACTURER") "Susumu Co Ltd")
        (field (name "VALUEDISPLAYED") "100")
        (field (name "PUBLISHER") "Texas Instruments")
      )
      (libsource (lib "Altium Vault - TI") (part "Resistor"))
    )
    (comp (ref "R48")
      (value "RG1005P-101-B-T5")
      (footprint "0402")
      (description "RES, 100, 0.1%, 0.063 W, 0402")
      (fields
        (field (name "MANUFACTURER") "Susumu Co Ltd")
        (field (name "VALUEDISPLAYED") "100")
        (field (name "PUBLISHER") "Texas Instruments")
      )
      (libsource (lib "Altium Vault - TI") (part "Resistor"))
    )
    (comp (ref "R49")
      (value "RG1005P-101-B-T5")
      (footprint "0402")
      (description "RES, 100, 0.1%, 0.063 W, 0402")
      (fields
        (field (name "MANUFACTURER") "Susumu Co Ltd")
        (field (name "VALUEDISPLAYED") "100")
        (field (name "PUBLISHER") "Texas Instruments")
      )
      (libsource (lib "Altium Vault - TI") (part "Resistor"))
    )
    (comp (ref "R50")
      (value "RG1005P-101-B-T5")
      (footprint "0402")
      (description "RES, 100, 0.1%, 0.063 W, 0402")
      (fields
        (field (name "MANUFACTURER") "Susumu Co Ltd")
        (field (name "VALUEDISPLAYED") "100")
        (field (name "PUBLISHER") "Texas Instruments")
      )
      (libsource (lib "Altium Vault - TI") (part "Resistor"))
    )
    (comp (ref "R51")
      (value "RG1005P-101-B-T5")
      (footprint "0402")
      (description "RES, 100, 0.1%, 0.063 W, 0402")
      (fields
        (field (name "MANUFACTURER") "Susumu Co Ltd")
        (field (name "VALUEDISPLAYED") "100")
        (field (name "PUBLISHER") "Texas Instruments")
      )
      (libsource (lib "Altium Vault - TI") (part "Resistor"))
    )
    (comp (ref "R53")
      (value "RG1005P-101-B-T5")
      (footprint "0402")
      (description "RES, 100, 0.1%, 0.063 W, 0402")
      (fields
        (field (name "MANUFACTURER") "Susumu Co Ltd")
        (field (name "VALUEDISPLAYED") "100")
        (field (name "PUBLISHER") "Texas Instruments")
      )
      (libsource (lib "Altium Vault - TI") (part "Resistor"))
    )
    (comp (ref "R54")
      (value "RG1005P-101-B-T5")
      (footprint "0402")
      (description "RES, 100, 0.1%, 0.063 W, 0402")
      (fields
        (field (name "MANUFACTURER") "Susumu Co Ltd")
        (field (name "VALUEDISPLAYED") "100")
        (field (name "PUBLISHER") "Texas Instruments")
      )
      (libsource (lib "Altium Vault - TI") (part "Resistor"))
    )
    (comp (ref "R55")
      (value "RG1005P-101-B-T5")
      (footprint "0402")
      (description "RES, 100, 0.1%, 0.063 W, 0402")
      (fields
        (field (name "MANUFACTURER") "Susumu Co Ltd")
        (field (name "VALUEDISPLAYED") "100")
        (field (name "PUBLISHER") "Texas Instruments")
      )
      (libsource (lib "Altium Vault - TI") (part "Resistor"))
    )
    (comp (ref "R56")
      (value "RG1005P-101-B-T5")
      (footprint "0402")
      (description "RES, 100, 0.1%, 0.063 W, 0402")
      (fields
        (field (name "MANUFACTURER") "Susumu Co Ltd")
        (field (name "VALUEDISPLAYED") "100")
        (field (name "PUBLISHER") "Texas Instruments")
      )
      (libsource (lib "Altium Vault - TI") (part "Resistor"))
    )
    (comp (ref "R57")
      (value "RG1005P-101-B-T5")
      (footprint "0402")
      (description "RES, 100, 0.1%, 0.063 W, 0402")
      (fields
        (field (name "MANUFACTURER") "Susumu Co Ltd")
        (field (name "VALUEDISPLAYED") "100")
        (field (name "PUBLISHER") "Texas Instruments")
      )
      (libsource (lib "Altium Vault - TI") (part "Resistor"))
    )
    (comp (ref "R58")
      (value "RG1005P-101-B-T5")
      (footprint "0402")
      (description "RES, 100, 0.1%, 0.063 W, 0402")
      (fields
        (field (name "MANUFACTURER") "Susumu Co Ltd")
        (field (name "VALUEDISPLAYED") "100")
        (field (name "PUBLISHER") "Texas Instruments")
      )
      (libsource (lib "Altium Vault - TI") (part "Resistor"))
    )
    (comp (ref "R59")
      (value "RG1005P-101-B-T5")
      (footprint "0402")
      (description "RES, 100, 0.1%, 0.063 W, 0402")
      (fields
        (field (name "MANUFACTURER") "Susumu Co Ltd")
        (field (name "VALUEDISPLAYED") "100")
        (field (name "PUBLISHER") "Texas Instruments")
      )
      (libsource (lib "Altium Vault - TI") (part "Resistor"))
    )
    (comp (ref "R60")
      (value "RG1005P-101-B-T5")
      (footprint "0402")
      (description "RES, 100, 0.1%, 0.063 W, 0402")
      (fields
        (field (name "MANUFACTURER") "Susumu Co Ltd")
        (field (name "VALUEDISPLAYED") "100")
        (field (name "PUBLISHER") "Texas Instruments")
      )
      (libsource (lib "Altium Vault - TI") (part "Resistor"))
    )
    (comp (ref "R63")
      (value "RG1005P-101-B-T5")
      (footprint "0402")
      (description "RES, 100, 0.1%, 0.063 W, 0402")
      (fields
        (field (name "MANUFACTURER") "Susumu Co Ltd")
        (field (name "VALUEDISPLAYED") "100")
        (field (name "PUBLISHER") "Texas Instruments")
      )
      (libsource (lib "Altium Vault - TI") (part "Resistor"))
    )
    (comp (ref "R64")
      (value "RG1005P-101-B-T5")
      (footprint "0402")
      (description "RES, 100, 0.1%, 0.063 W, 0402")
      (fields
        (field (name "MANUFACTURER") "Susumu Co Ltd")
        (field (name "VALUEDISPLAYED") "100")
        (field (name "PUBLISHER") "Texas Instruments")
      )
      (libsource (lib "Altium Vault - TI") (part "Resistor"))
    )
    (comp (ref "R68")
      (value "RG1005P-101-B-T5")
      (footprint "0402")
      (description "RES, 100, 0.1%, 0.063 W, 0402")
      (fields
        (field (name "MANUFACTURER") "Susumu Co Ltd")
        (field (name "VALUEDISPLAYED") "100")
        (field (name "PUBLISHER") "Texas Instruments")
      )
      (libsource (lib "Altium Vault - TI") (part "Resistor"))
    )
    (comp (ref "R69")
      (value "RG1005P-101-B-T5")
      (footprint "0402")
      (description "RES, 100, 0.1%, 0.063 W, 0402")
      (fields
        (field (name "MANUFACTURER") "Susumu Co Ltd")
        (field (name "VALUEDISPLAYED") "100")
        (field (name "PUBLISHER") "Texas Instruments")
      )
      (libsource (lib "Altium Vault - TI") (part "Resistor"))
    )
    (comp (ref "R70")
      (value "RG1005P-101-B-T5")
      (footprint "0402")
      (description "RES, 100, 0.1%, 0.063 W, 0402")
      (fields
        (field (name "MANUFACTURER") "Susumu Co Ltd")
        (field (name "VALUEDISPLAYED") "100")
        (field (name "PUBLISHER") "Texas Instruments")
      )
      (libsource (lib "Altium Vault - TI") (part "Resistor"))
    )
    (comp (ref "R71")
      (value "RG1005P-101-B-T5")
      (footprint "0402")
      (description "RES, 100, 0.1%, 0.063 W, 0402")
      (fields
        (field (name "MANUFACTURER") "Susumu Co Ltd")
        (field (name "VALUEDISPLAYED") "100")
        (field (name "PUBLISHER") "Texas Instruments")
      )
      (libsource (lib "Altium Vault - TI") (part "Resistor"))
    )
    (comp (ref "R75")
      (value "RG1005P-101-B-T5")
      (footprint "0402")
      (description "RES, 100, 0.1%, 0.063 W, 0402")
      (fields
        (field (name "MANUFACTURER") "Susumu Co Ltd")
        (field (name "VALUEDISPLAYED") "100")
        (field (name "PUBLISHER") "Texas Instruments")
      )
      (libsource (lib "Altium Vault - TI") (part "Resistor"))
    )
    (comp (ref "R76")
      (value "RG1005P-101-B-T5")
      (footprint "0402")
      (description "RES, 100, 0.1%, 0.063 W, 0402")
      (fields
        (field (name "MANUFACTURER") "Susumu Co Ltd")
        (field (name "VALUEDISPLAYED") "100")
        (field (name "PUBLISHER") "Texas Instruments")
      )
      (libsource (lib "Altium Vault - TI") (part "Resistor"))
    )
    (comp (ref "R80")
      (value "RG1005P-101-B-T5")
      (footprint "0402")
      (description "RES, 100, 0.1%, 0.063 W, 0402")
      (fields
        (field (name "MANUFACTURER") "Susumu Co Ltd")
        (field (name "VALUEDISPLAYED") "100")
        (field (name "PUBLISHER") "Texas Instruments")
      )
      (libsource (lib "Altium Vault - TI") (part "Resistor"))
    )
    (comp (ref "R81")
      (value "RG1005P-101-B-T5")
      (footprint "0402")
      (description "RES, 100, 0.1%, 0.063 W, 0402")
      (fields
        (field (name "MANUFACTURER") "Susumu Co Ltd")
        (field (name "VALUEDISPLAYED") "100")
        (field (name "PUBLISHER") "Texas Instruments")
      )
      (libsource (lib "Altium Vault - TI") (part "Resistor"))
    )
    (comp (ref "R82")
      (value "RG1005P-101-B-T5")
      (footprint "0402")
      (description "RES, 100, 0.1%, 0.063 W, 0402")
      (fields
        (field (name "MANUFACTURER") "Susumu Co Ltd")
        (field (name "VALUEDISPLAYED") "100")
        (field (name "PUBLISHER") "Texas Instruments")
      )
      (libsource (lib "Altium Vault - TI") (part "Resistor"))
    )
    (comp (ref "R83")
      (value "RG1005P-101-B-T5")
      (footprint "0402")
      (description "RES, 100, 0.1%, 0.063 W, 0402")
      (fields
        (field (name "MANUFACTURER") "Susumu Co Ltd")
        (field (name "VALUEDISPLAYED") "100")
        (field (name "PUBLISHER") "Texas Instruments")
      )
      (libsource (lib "Altium Vault - TI") (part "Resistor"))
    )
    (comp (ref "R84")
      (value "RG1005P-101-B-T5")
      (footprint "0402")
      (description "RES, 100, 0.1%, 0.063 W, 0402")
      (fields
        (field (name "MANUFACTURER") "Susumu Co Ltd")
        (field (name "VALUEDISPLAYED") "100")
        (field (name "PUBLISHER") "Texas Instruments")
      )
      (libsource (lib "Altium Vault - TI") (part "Resistor"))
    )
    (comp (ref "R85")
      (value "RG1005P-101-B-T5")
      (footprint "0402")
      (description "RES, 100, 0.1%, 0.063 W, 0402")
      (fields
        (field (name "MANUFACTURER") "Susumu Co Ltd")
        (field (name "VALUEDISPLAYED") "100")
        (field (name "PUBLISHER") "Texas Instruments")
      )
      (libsource (lib "Altium Vault - TI") (part "Resistor"))
    )
    (comp (ref "R87")
      (value "RG1005P-101-B-T5")
      (footprint "0402")
      (description "RES, 100, 0.1%, 0.063 W, 0402")
      (fields
        (field (name "MANUFACTURER") "Susumu Co Ltd")
        (field (name "VALUEDISPLAYED") "100")
        (field (name "PUBLISHER") "Texas Instruments")
      )
      (libsource (lib "Altium Vault - TI") (part "Resistor"))
    )
    (comp (ref "R90")
      (value "RG1005P-101-B-T5")
      (footprint "0402")
      (description "RES, 100, 0.1%, 0.063 W, 0402")
      (fields
        (field (name "MANUFACTURER") "Susumu Co Ltd")
        (field (name "VALUEDISPLAYED") "100")
        (field (name "PUBLISHER") "Texas Instruments")
      )
      (libsource (lib "Altium Vault - TI") (part "Resistor"))
    )
    (comp (ref "R93")
      (value "RG1005P-101-B-T5")
      (footprint "0402")
      (description "RES, 100, 0.1%, 0.063 W, 0402")
      (fields
        (field (name "MANUFACTURER") "Susumu Co Ltd")
        (field (name "VALUEDISPLAYED") "100")
        (field (name "PUBLISHER") "Texas Instruments")
      )
      (libsource (lib "Altium Vault - TI") (part "Resistor"))
    )
    (comp (ref "R94")
      (value "RG1005P-101-B-T5")
      (footprint "0402")
      (description "RES, 100, 0.1%, 0.063 W, 0402")
      (fields
        (field (name "MANUFACTURER") "Susumu Co Ltd")
        (field (name "VALUEDISPLAYED") "100")
        (field (name "PUBLISHER") "Texas Instruments")
      )
      (libsource (lib "Altium Vault - TI") (part "Resistor"))
    )
    (comp (ref "R95")
      (value "RG1005P-101-B-T5")
      (footprint "0402")
      (description "RES, 100, 0.1%, 0.063 W, 0402")
      (fields
        (field (name "MANUFACTURER") "Susumu Co Ltd")
        (field (name "VALUEDISPLAYED") "100")
        (field (name "PUBLISHER") "Texas Instruments")
      )
      (libsource (lib "Altium Vault - TI") (part "Resistor"))
    )
    (comp (ref "R96")
      (value "RG1005P-101-B-T5")
      (footprint "0402")
      (description "RES, 100, 0.1%, 0.063 W, 0402")
      (fields
        (field (name "MANUFACTURER") "Susumu Co Ltd")
        (field (name "VALUEDISPLAYED") "100")
        (field (name "PUBLISHER") "Texas Instruments")
      )
      (libsource (lib "Altium Vault - TI") (part "Resistor"))
    )
    (comp (ref "R97")
      (value "RG1005P-101-B-T5")
      (footprint "0402")
      (description "RES, 100, 0.1%, 0.063 W, 0402")
      (fields
        (field (name "MANUFACTURER") "Susumu Co Ltd")
        (field (name "VALUEDISPLAYED") "100")
        (field (name "PUBLISHER") "Texas Instruments")
      )
      (libsource (lib "Altium Vault - TI") (part "Resistor"))
    )
    (comp (ref "R98")
      (value "RG1005P-101-B-T5")
      (footprint "0402")
      (description "RES, 100, 0.1%, 0.063 W, 0402")
      (fields
        (field (name "MANUFACTURER") "Susumu Co Ltd")
        (field (name "VALUEDISPLAYED") "100")
        (field (name "PUBLISHER") "Texas Instruments")
      )
      (libsource (lib "Altium Vault - TI") (part "Resistor"))
    )
    (comp (ref "R99")
      (value "RG1005P-101-B-T5")
      (footprint "0402")
      (description "RES, 100, 0.1%, 0.063 W, 0402")
      (fields
        (field (name "MANUFACTURER") "Susumu Co Ltd")
        (field (name "VALUEDISPLAYED") "100")
        (field (name "PUBLISHER") "Texas Instruments")
      )
      (libsource (lib "Altium Vault - TI") (part "Resistor"))
    )
    (comp (ref "R101")
      (value "RG1005P-101-B-T5")
      (footprint "0402")
      (description "RES, 100, 0.1%, 0.063 W, 0402")
      (fields
        (field (name "MANUFACTURER") "Susumu Co Ltd")
        (field (name "VALUEDISPLAYED") "100")
        (field (name "PUBLISHER") "Texas Instruments")
      )
      (libsource (lib "Altium Vault - TI") (part "Resistor"))
    )
    (comp (ref "R102")
      (value "RG1005P-101-B-T5")
      (footprint "0402")
      (description "RES, 100, 0.1%, 0.063 W, 0402")
      (fields
        (field (name "MANUFACTURER") "Susumu Co Ltd")
        (field (name "VALUEDISPLAYED") "100")
        (field (name "PUBLISHER") "Texas Instruments")
      )
      (libsource (lib "Altium Vault - TI") (part "Resistor"))
    )
    (comp (ref "R106")
      (value "RG1005P-101-B-T5")
      (footprint "0402")
      (description "RES, 100, 0.1%, 0.063 W, 0402")
      (fields
        (field (name "MANUFACTURER") "Susumu Co Ltd")
        (field (name "VALUEDISPLAYED") "100")
        (field (name "PUBLISHER") "Texas Instruments")
      )
      (libsource (lib "Altium Vault - TI") (part "Resistor"))
    )
    (comp (ref "R107")
      (value "RG1005P-101-B-T5")
      (footprint "0402")
      (description "RES, 100, 0.1%, 0.063 W, 0402")
      (fields
        (field (name "MANUFACTURER") "Susumu Co Ltd")
        (field (name "VALUEDISPLAYED") "100")
        (field (name "PUBLISHER") "Texas Instruments")
      )
      (libsource (lib "Altium Vault - TI") (part "Resistor"))
    )
    (comp (ref "R117")
      (value "RG1005P-101-B-T5")
      (footprint "0402")
      (description "RES, 100, 0.1%, 0.063 W, 0402")
      (fields
        (field (name "MANUFACTURER") "Susumu Co Ltd")
        (field (name "VALUEDISPLAYED") "100")
        (field (name "PUBLISHER") "Texas Instruments")
      )
      (libsource (lib "Altium Vault - TI") (part "Resistor"))
    )
    (comp (ref "R121")
      (value "RG1005P-101-B-T5")
      (footprint "0402")
      (description "RES, 100, 0.1%, 0.063 W, 0402")
      (fields
        (field (name "MANUFACTURER") "Susumu Co Ltd")
        (field (name "VALUEDISPLAYED") "100")
        (field (name "PUBLISHER") "Texas Instruments")
      )
      (libsource (lib "Altium Vault - TI") (part "Resistor"))
    )
    (comp (ref "R159")
      (value "RG1005P-101-B-T5")
      (footprint "0402")
      (description "RES, 100, 0.1%, 0.063 W, 0402")
      (fields
        (field (name "MANUFACTURER") "Susumu Co Ltd")
        (field (name "VALUEDISPLAYED") "100")
        (field (name "PUBLISHER") "Texas Instruments")
      )
      (libsource (lib "Altium Vault - TI") (part "Resistor"))
    )
    (comp (ref "R237")
      (value "RG1005P-101-B-T5")
      (footprint "0402")
      (description "RES, 100, 0.1%, 0.063 W, 0402")
      (fields
        (field (name "MANUFACTURER") "Susumu Co Ltd")
        (field (name "VALUEDISPLAYED") "100")
        (field (name "PUBLISHER") "Texas Instruments")
      )
      (libsource (lib "Altium Vault - TI") (part "Resistor"))
    )
    (comp (ref "R238")
      (value "RG1005P-101-B-T5")
      (footprint "0402")
      (description "RES, 100, 0.1%, 0.063 W, 0402")
      (fields
        (field (name "MANUFACTURER") "Susumu Co Ltd")
        (field (name "VALUEDISPLAYED") "100")
        (field (name "PUBLISHER") "Texas Instruments")
      )
      (libsource (lib "Altium Vault - TI") (part "Resistor"))
    )
    (comp (ref "R239")
      (value "RG1005P-101-B-T5")
      (footprint "0402")
      (description "RES, 100, 0.1%, 0.063 W, 0402")
      (fields
        (field (name "MANUFACTURER") "Susumu Co Ltd")
        (field (name "VALUEDISPLAYED") "100")
        (field (name "PUBLISHER") "Texas Instruments")
      )
      (libsource (lib "Altium Vault - TI") (part "Resistor"))
    )
    (comp (ref "R255")
      (value "RG1005P-101-B-T5")
      (footprint "0402")
      (description "RES, 100, 0.1%, 0.063 W, 0402")
      (fields
        (field (name "MANUFACTURER") "Susumu Co Ltd")
        (field (name "VALUEDISPLAYED") "100")
        (field (name "PUBLISHER") "Texas Instruments")
      )
      (libsource (lib "Altium Vault - TI") (part "Resistor"))
    )
    (comp (ref "R256")
      (value "RG1005P-101-B-T5")
      (footprint "0402")
      (description "RES, 100, 0.1%, 0.063 W, 0402")
      (fields
        (field (name "MANUFACTURER") "Susumu Co Ltd")
        (field (name "VALUEDISPLAYED") "100")
        (field (name "PUBLISHER") "Texas Instruments")
      )
      (libsource (lib "Altium Vault - TI") (part "Resistor"))
    )
    (comp (ref "R257")
      (value "RG1005P-101-B-T5")
      (footprint "0402")
      (description "RES, 100, 0.1%, 0.063 W, 0402")
      (fields
        (field (name "MANUFACTURER") "Susumu Co Ltd")
        (field (name "VALUEDISPLAYED") "100")
        (field (name "PUBLISHER") "Texas Instruments")
      )
      (libsource (lib "Altium Vault - TI") (part "Resistor"))
    )
    (comp (ref "R258")
      (value "RG1005P-101-B-T5")
      (footprint "0402")
      (description "RES, 100, 0.1%, 0.063 W, 0402")
      (fields
        (field (name "MANUFACTURER") "Susumu Co Ltd")
        (field (name "VALUEDISPLAYED") "100")
        (field (name "PUBLISHER") "Texas Instruments")
      )
      (libsource (lib "Altium Vault - TI") (part "Resistor"))
    )
    (comp (ref "R259")
      (value "RG1005P-101-B-T5")
      (footprint "0402")
      (description "RES, 100, 0.1%, 0.063 W, 0402")
      (fields
        (field (name "MANUFACTURER") "Susumu Co Ltd")
        (field (name "VALUEDISPLAYED") "100")
        (field (name "PUBLISHER") "Texas Instruments")
      )
      (libsource (lib "Altium Vault - TI") (part "Resistor"))
    )
    (comp (ref "R260")
      (value "RG1005P-101-B-T5")
      (footprint "0402")
      (description "RES, 100, 0.1%, 0.063 W, 0402")
      (fields
        (field (name "MANUFACTURER") "Susumu Co Ltd")
        (field (name "VALUEDISPLAYED") "100")
        (field (name "PUBLISHER") "Texas Instruments")
      )
      (libsource (lib "Altium Vault - TI") (part "Resistor"))
    )
    (comp (ref "R261")
      (value "RG1005P-101-B-T5")
      (footprint "0402")
      (description "RES, 100, 0.1%, 0.063 W, 0402")
      (fields
        (field (name "MANUFACTURER") "Susumu Co Ltd")
        (field (name "VALUEDISPLAYED") "100")
        (field (name "PUBLISHER") "Texas Instruments")
      )
      (libsource (lib "Altium Vault - TI") (part "Resistor"))
    )
    (comp (ref "R281")
      (value "RG1005P-101-B-T5")
      (footprint "0402")
      (description "RES, 100, 0.1%, 0.063 W, 0402")
      (fields
        (field (name "MANUFACTURER") "Susumu Co Ltd")
        (field (name "VALUEDISPLAYED") "100")
        (field (name "PUBLISHER") "Texas Instruments")
      )
      (libsource (lib "Altium Vault - TI") (part "Resistor"))
    )
    (comp (ref "R282")
      (value "RG1005P-101-B-T5")
      (footprint "0402")
      (description "RES, 100, 0.1%, 0.063 W, 0402")
      (fields
        (field (name "MANUFACTURER") "Susumu Co Ltd")
        (field (name "VALUEDISPLAYED") "100")
        (field (name "PUBLISHER") "Texas Instruments")
      )
      (libsource (lib "Altium Vault - TI") (part "Resistor"))
    )
    (comp (ref "R287")
      (value "RG1005P-101-B-T5")
      (footprint "0402")
      (description "RES, 100, 0.1%, 0.063 W, 0402")
      (fields
        (field (name "MANUFACTURER") "Susumu Co Ltd")
        (field (name "VALUEDISPLAYED") "100")
        (field (name "PUBLISHER") "Texas Instruments")
      )
      (libsource (lib "Altium Vault - TI") (part "Resistor"))
    )
    (comp (ref "R288")
      (value "RG1005P-101-B-T5")
      (footprint "0402")
      (description "RES, 100, 0.1%, 0.063 W, 0402")
      (fields
        (field (name "MANUFACTURER") "Susumu Co Ltd")
        (field (name "VALUEDISPLAYED") "100")
        (field (name "PUBLISHER") "Texas Instruments")
      )
      (libsource (lib "Altium Vault - TI") (part "Resistor"))
    )
    (comp (ref "R289")
      (value "RG1005P-101-B-T5")
      (footprint "0402")
      (description "RES, 100, 0.1%, 0.063 W, 0402")
      (fields
        (field (name "MANUFACTURER") "Susumu Co Ltd")
        (field (name "VALUEDISPLAYED") "100")
        (field (name "PUBLISHER") "Texas Instruments")
      )
      (libsource (lib "Altium Vault - TI") (part "Resistor"))
    )
    (comp (ref "R291")
      (value "RG1005P-101-B-T5")
      (footprint "0402")
      (description "RES, 100, 0.1%, 0.063 W, 0402")
      (fields
        (field (name "MANUFACTURER") "Susumu Co Ltd")
        (field (name "VALUEDISPLAYED") "100")
        (field (name "PUBLISHER") "Texas Instruments")
      )
      (libsource (lib "Altium Vault - TI") (part "Resistor"))
    )
    (comp (ref "R328")
      (value "RG1005P-101-B-T5")
      (footprint "0402")
      (description "RES, 100, 0.1%, 0.063 W, 0402")
      (fields
        (field (name "MANUFACTURER") "Susumu Co Ltd")
        (field (name "VALUEDISPLAYED") "100")
        (field (name "PUBLISHER") "Texas Instruments")
      )
      (libsource (lib "Altium Vault - TI") (part "Resistor"))
    )
    (comp (ref "R343")
      (value "RG1005P-101-B-T5")
      (footprint "0402")
      (description "RES, 100, 0.1%, 0.063 W, 0402")
      (fields
        (field (name "MANUFACTURER") "Susumu Co Ltd")
        (field (name "VALUEDISPLAYED") "100")
        (field (name "PUBLISHER") "Texas Instruments")
      )
      (libsource (lib "Altium Vault - TI") (part "Resistor"))
    )
    (comp (ref "R349")
      (value "RG1005P-101-B-T5")
      (footprint "0402")
      (description "RES, 100, 0.1%, 0.063 W, 0402")
      (fields
        (field (name "MANUFACTURER") "Susumu Co Ltd")
        (field (name "VALUEDISPLAYED") "100")
        (field (name "PUBLISHER") "Texas Instruments")
      )
      (libsource (lib "Altium Vault - TI") (part "Resistor"))
    )
    (comp (ref "R359")
      (value "RG1005P-101-B-T5")
      (footprint "0402")
      (description "RES, 100, 0.1%, 0.063 W, 0402")
      (fields
        (field (name "MANUFACTURER") "Susumu Co Ltd")
        (field (name "VALUEDISPLAYED") "100")
        (field (name "PUBLISHER") "Texas Instruments")
      )
      (libsource (lib "Altium Vault - TI") (part "Resistor"))
    )
    (comp (ref "TP69")
      (value "TESTPOINT")
      (footprint "TP_50MIL-SMT")
      (description "TEST POINT.  No entry in BOM.")
      (libsource (lib "Altium Vault - TI") (part "TESTPOINT"))
    )
    (comp (ref "TP70")
      (value "TESTPOINT")
      (footprint "TP_50MIL-SMT")
      (description "TEST POINT.  No entry in BOM.")
      (libsource (lib "Altium Vault - TI") (part "TESTPOINT"))
    )
    (comp (ref "TP71")
      (value "TESTPOINT")
      (footprint "TP_50MIL-SMT")
      (description "TEST POINT.  No entry in BOM.")
      (libsource (lib "Altium Vault - TI") (part "TESTPOINT"))
    )
    (comp (ref "TP72")
      (value "TESTPOINT")
      (footprint "TP_50MIL-SMT")
      (description "TEST POINT.  No entry in BOM.")
      (libsource (lib "Altium Vault - TI") (part "TESTPOINT"))
    )
    (comp (ref "TP73")
      (value "TESTPOINT")
      (footprint "TP_50MIL-SMT")
      (description "TEST POINT.  No entry in BOM.")
      (libsource (lib "Altium Vault - TI") (part "TESTPOINT"))
    )
    (comp (ref "TP74")
      (value "TESTPOINT")
      (footprint "TP_50MIL-SMT")
      (description "TEST POINT.  No entry in BOM.")
      (libsource (lib "Altium Vault - TI") (part "TESTPOINT"))
    )
    (comp (ref "TP75")
      (value "TESTPOINT")
      (footprint "TP_50MIL-SMT")
      (description "TEST POINT.  No entry in BOM.")
      (libsource (lib "Altium Vault - TI") (part "TESTPOINT"))
    )
    (comp (ref "TP76")
      (value "TESTPOINT")
      (footprint "TP_50MIL-SMT")
      (description "TEST POINT.  No entry in BOM.")
      (libsource (lib "Altium Vault - TI") (part "TESTPOINT"))
    )
    (comp (ref "TP77")
      (value "TESTPOINT")
      (footprint "TP_50MIL-SMT")
      (description "TEST POINT.  No entry in BOM.")
      (libsource (lib "Altium Vault - TI") (part "TESTPOINT"))
    )
    (comp (ref "TP78")
      (value "TESTPOINT")
      (footprint "TP_50MIL-SMT")
      (description "TEST POINT.  No entry in BOM.")
      (libsource (lib "Altium Vault - TI") (part "TESTPOINT"))
    )
    (comp (ref "TP79")
      (value "TESTPOINT")
      (footprint "TP_50MIL-SMT")
      (description "TEST POINT.  No entry in BOM.")
      (libsource (lib "Altium Vault - TI") (part "TESTPOINT"))
    )
    (comp (ref "TP80")
      (value "TESTPOINT")
      (footprint "TP_50MIL-SMT")
      (description "TEST POINT.  No entry in BOM.")
      (libsource (lib "Altium Vault - TI") (part "TESTPOINT"))
    )
    (comp (ref "TP81")
      (value "TESTPOINT")
      (footprint "TP_50MIL-SMT")
      (description "TEST POINT.  No entry in BOM.")
      (libsource (lib "Altium Vault - TI") (part "TESTPOINT"))
    )
    (comp (ref "TP82")
      (value "TESTPOINT")
      (footprint "TP_50MIL-SMT")
      (description "TEST POINT.  No entry in BOM.")
      (libsource (lib "Altium Vault - TI") (part "TESTPOINT"))
    )
    (comp (ref "TP83")
      (value "TESTPOINT")
      (footprint "TP_50MIL-SMT")
      (description "TEST POINT.  No entry in BOM.")
      (libsource (lib "Altium Vault - TI") (part "TESTPOINT"))
    )
    (comp (ref "TP84")
      (value "TESTPOINT")
      (footprint "TP_50MIL-SMT")
      (description "TEST POINT.  No entry in BOM.")
      (libsource (lib "Altium Vault - TI") (part "TESTPOINT"))
    )
    (comp (ref "TP101")
      (value "TESTPOINT")
      (footprint "TP_50MIL-SMT")
      (description "TEST POINT.  No entry in BOM.")
      (libsource (lib "Altium Vault - TI") (part "TESTPOINT"))
    )
    (comp (ref "TP102")
      (value "TESTPOINT")
      (footprint "TP_50MIL-SMT")
      (description "TEST POINT.  No entry in BOM.")
      (libsource (lib "Altium Vault - TI") (part "TESTPOINT"))
    )
    (comp (ref "TP103")
      (value "TESTPOINT")
      (footprint "TP_50MIL-SMT")
      (description "TEST POINT.  No entry in BOM.")
      (libsource (lib "Altium Vault - TI") (part "TESTPOINT"))
    )
    (comp (ref "TP104")
      (value "TESTPOINT")
      (footprint "TP_50MIL-SMT")
      (description "TEST POINT.  No entry in BOM.")
      (libsource (lib "Altium Vault - TI") (part "TESTPOINT"))
    )
    (comp (ref "TP105")
      (value "TESTPOINT")
      (footprint "TP_50MIL-SMT")
      (description "TEST POINT.  No entry in BOM.")
      (libsource (lib "Altium Vault - TI") (part "TESTPOINT"))
    )
    (comp (ref "TP106")
      (value "TESTPOINT")
      (footprint "TP_50MIL-SMT")
      (description "TEST POINT.  No entry in BOM.")
      (libsource (lib "Altium Vault - TI") (part "TESTPOINT"))
    )
    (comp (ref "TP107")
      (value "TESTPOINT")
      (footprint "TP_50MIL-SMT")
      (description "TEST POINT.  No entry in BOM.")
      (libsource (lib "Altium Vault - TI") (part "TESTPOINT"))
    )
    (comp (ref "TP108")
      (value "TESTPOINT")
      (footprint "TP_50MIL-SMT")
      (description "TEST POINT.  No entry in BOM.")
      (libsource (lib "Altium Vault - TI") (part "TESTPOINT"))
    )
    (comp (ref "TP109")
      (value "TESTPOINT")
      (footprint "TP_50MIL-SMT")
      (description "TEST POINT.  No entry in BOM.")
      (libsource (lib "Altium Vault - TI") (part "TESTPOINT"))
    )
    (comp (ref "TP110")
      (value "TESTPOINT")
      (footprint "TP_50MIL-SMT")
      (description "TEST POINT.  No entry in BOM.")
      (libsource (lib "Altium Vault - TI") (part "TESTPOINT"))
    )
    (comp (ref "TP111")
      (value "TESTPOINT")
      (footprint "TP_50MIL-SMT")
      (description "TEST POINT.  No entry in BOM.")
      (libsource (lib "Altium Vault - TI") (part "TESTPOINT"))
    )
    (comp (ref "TP112")
      (value "TESTPOINT")
      (footprint "TP_50MIL-SMT")
      (description "TEST POINT.  No entry in BOM.")
      (libsource (lib "Altium Vault - TI") (part "TESTPOINT"))
    )
    (comp (ref "TP113")
      (value "TESTPOINT")
      (footprint "TP_50MIL-SMT")
      (description "TEST POINT.  No entry in BOM.")
      (libsource (lib "Altium Vault - TI") (part "TESTPOINT"))
    )
    (comp (ref "TP114")
      (value "TESTPOINT")
      (footprint "TP_50MIL-SMT")
      (description "TEST POINT.  No entry in BOM.")
      (libsource (lib "Altium Vault - TI") (part "TESTPOINT"))
    )
    (comp (ref "TP115")
      (value "TESTPOINT")
      (footprint "TP_50MIL-SMT")
      (description "TEST POINT.  No entry in BOM.")
      (libsource (lib "Altium Vault - TI") (part "TESTPOINT"))
    )
    (comp (ref "TP116")
      (value "TESTPOINT")
      (footprint "TP_50MIL-SMT")
      (description "TEST POINT.  No entry in BOM.")
      (libsource (lib "Altium Vault - TI") (part "TESTPOINT"))
    )
  )
  (nets
    (net (code "2") (name "/RXP1") (class "Default")
      (node (ref "C179") (pin "1") (pinfunction "1_1") (pintype "passive"))
      (node (ref "J6") (pin "12") (pinfunction "12_12") (pintype "passive"))
      (node (ref "R94") (pin "2") (pinfunction "2_2") (pintype "passive"))
    )
    (net (code "3") (name "/RXP2") (class "Default")
      (node (ref "C195") (pin "1") (pinfunction "1_1") (pintype "passive"))
      (node (ref "J6") (pin "10") (pinfunction "10_10") (pintype "passive"))
      (node (ref "R239") (pin "2") (pinfunction "2_2") (pintype "passive"))
    )
    (net (code "4") (name "/RXP3") (class "Default")
      (node (ref "C188") (pin "1") (pinfunction "1_1") (pintype "passive"))
      (node (ref "J6") (pin "16") (pinfunction "16_16") (pintype "passive"))
      (node (ref "R107") (pin "2") (pinfunction "2_2") (pintype "passive"))
    )
    (net (code "5") (name "/RXP4") (class "Default")
      (node (ref "C204") (pin "1") (pinfunction "1_1") (pintype "passive"))
      (node (ref "J6") (pin "18") (pinfunction "18_18") (pintype "passive"))
      (node (ref "R282") (pin "2") (pinfunction "2_2") (pintype "passive"))
    )
    (net (code "6") (name "/RXP5") (class "Default")
      (node (ref "C79") (pin "1") (pinfunction "1_1") (pintype "passive"))
      (node (ref "J5") (pin "10") (pinfunction "10_10") (pintype "passive"))
      (node (ref "R55") (pin "2") (pinfunction "2_2") (pintype "passive"))
    )
    (net (code "7") (name "/RXP6") (class "Default")
      (node (ref "C95") (pin "1") (pinfunction "1_1") (pintype "passive"))
      (node (ref "J5") (pin "12") (pinfunction "12_12") (pintype "passive"))
      (node (ref "R81") (pin "2") (pinfunction "2_2") (pintype "passive"))
    )
    (net (code "8") (name "/RXP7") (class "Default")
      (node (ref "C189") (pin "1") (pinfunction "1_1") (pintype "passive"))
      (node (ref "J6") (pin "22") (pinfunction "22_22") (pintype "passive"))
      (node (ref "R117") (pin "2") (pinfunction "2_2") (pintype "passive"))
    )
    (net (code "9") (name "/RXP8") (class "Default")
      (node (ref "C205") (pin "1") (pinfunction "1_1") (pintype "passive"))
      (node (ref "J6") (pin "24") (pinfunction "24_24") (pintype "passive"))
      (node (ref "R287") (pin "2") (pinfunction "2_2") (pintype "passive"))
    )
    (net (code "10") (name "/RXP9") (class "Default")
      (node (ref "C186") (pin "1") (pinfunction "1_1") (pintype "passive"))
      (node (ref "J6") (pin "17") (pinfunction "17_17") (pintype "passive"))
      (node (ref "R102") (pin "2") (pinfunction "2_2") (pintype "passive"))
      (node (ref "TP69") (pin "1") (pintype "passive"))
    )
    (net (code "11") (name "/RXP10") (class "Default")
      (node (ref "C202") (pin "1") (pinfunction "1_1") (pintype "passive"))
      (node (ref "J6") (pin "15") (pinfunction "15_15") (pintype "passive"))
      (node (ref "R261") (pin "2") (pinfunction "2_2") (pintype "passive"))
      (node (ref "TP70") (pin "1") (pintype "passive"))
    )
    (net (code "12") (name "/RXP11") (class "Default")
      (node (ref "C71") (pin "1") (pinfunction "1_1") (pintype "passive"))
      (node (ref "J5") (pin "4") (pinfunction "4_4") (pintype "passive"))
      (node (ref "R46") (pin "2") (pinfunction "2_2") (pintype "passive"))
    )
    (net (code "13") (name "/RXP12") (class "Default")
      (node (ref "C87") (pin "1") (pinfunction "1_1") (pintype "passive"))
      (node (ref "J5") (pin "6") (pinfunction "6_6") (pintype "passive"))
      (node (ref "R64") (pin "2") (pinfunction "2_2") (pintype "passive"))
    )
    (net (code "14") (name "/RXP13") (class "Default")
      (node (ref "C181") (pin "1") (pinfunction "1_1") (pintype "passive"))
      (node (ref "J5") (pin "22") (pinfunction "22_22") (pintype "passive"))
      (node (ref "R96") (pin "2") (pinfunction "2_2") (pintype "passive"))
    )
    (net (code "15") (name "/RXP14") (class "Default")
      (node (ref "C197") (pin "1") (pinfunction "1_1") (pintype "passive"))
      (node (ref "J5") (pin "24") (pinfunction "24_24") (pintype "passive"))
      (node (ref "R256") (pin "2") (pinfunction "2_2") (pintype "passive"))
    )
    (net (code "16") (name "/RXP15") (class "Default")
      (node (ref "C74") (pin "1") (pinfunction "1_1") (pintype "passive"))
      (node (ref "J5") (pin "23") (pinfunction "23_23") (pintype "passive"))
      (node (ref "R49") (pin "2") (pinfunction "2_2") (pintype "passive"))
      (node (ref "TP101") (pin "1") (pintype "passive"))
    )
    (net (code "17") (name "/RXP16") (class "Default")
      (node (ref "C90") (pin "1") (pinfunction "1_1") (pintype "passive"))
      (node (ref "J5") (pin "21") (pinfunction "21_21") (pintype "passive"))
      (node (ref "R70") (pin "2") (pinfunction "2_2") (pintype "passive"))
      (node (ref "TP105") (pin "1") (pintype "passive"))
    )
    (net (code "18") (name "/RXP17") (class "Default")
      (node (ref "C78") (pin "1") (pinfunction "1_1") (pintype "passive"))
      (node (ref "J6") (pin "21") (pinfunction "21_21") (pintype "passive"))
      (node (ref "R54") (pin "2") (pinfunction "2_2") (pintype "passive"))
      (node (ref "TP71") (pin "1") (pintype "passive"))
    )
    (net (code "19") (name "/RXP18") (class "Default")
      (node (ref "C94") (pin "1") (pinfunction "1_1") (pintype "passive"))
      (node (ref "J6") (pin "23") (pinfunction "23_23") (pintype "passive"))
      (node (ref "R80") (pin "2") (pinfunction "2_2") (pintype "passive"))
      (node (ref "TP72") (pin "1") (pintype "passive"))
    )
    (net (code "20") (name "/RXP19") (class "Default")
      (node (ref "C72") (pin "1") (pinfunction "1_1") (pintype "passive"))
      (node (ref "J5") (pin "5") (pinfunction "5_5") (pintype "passive"))
      (node (ref "R47") (pin "2") (pinfunction "2_2") (pintype "passive"))
      (node (ref "TP102") (pin "1") (pintype "passive"))
    )
    (net (code "21") (name "/RXP20") (class "Default")
      (node (ref "C88") (pin "1") (pinfunction "1_1") (pintype "passive"))
      (node (ref "J5") (pin "3") (pinfunction "3_3") (pintype "passive"))
      (node (ref "R68") (pin "2") (pinfunction "2_2") (pintype "passive"))
      (node (ref "TP106") (pin "1") (pintype "passive"))
    )
    (net (code "22") (name "/RXP21") (class "Default")
      (node (ref "C187") (pin "1") (pinfunction "1_1") (pintype "passive"))
      (node (ref "J5") (pin "11") (pinfunction "11_11") (pintype "passive"))
      (node (ref "R106") (pin "2") (pinfunction "2_2") (pintype "passive"))
      (node (ref "TP103") (pin "1") (pintype "passive"))
    )
    (net (code "23") (name "/RXP22") (class "Default")
      (node (ref "C203") (pin "1") (pinfunction "1_1") (pintype "passive"))
      (node (ref "J5") (pin "9") (pinfunction "9_9") (pintype "passive"))
      (node (ref "R281") (pin "2") (pinfunction "2_2") (pintype "passive"))
      (node (ref "TP107") (pin "1") (pintype "passive"))
    )
    (net (code "24") (name "/RXP23") (class "Default")
      (node (ref "C180") (pin "1") (pinfunction "1_1") (pintype "passive"))
      (node (ref "J5") (pin "15") (pinfunction "15_15") (pintype "passive"))
      (node (ref "R95") (pin "2") (pinfunction "2_2") (pintype "passive"))
      (node (ref "TP104") (pin "1") (pintype "passive"))
    )
    (net (code "25") (name "/RXP24") (class "Default")
      (node (ref "C196") (pin "1") (pinfunction "1_1") (pintype "passive"))
      (node (ref "J5") (pin "17") (pinfunction "17_17") (pintype "passive"))
      (node (ref "R255") (pin "2") (pinfunction "2_2") (pintype "passive"))
      (node (ref "TP108") (pin "1") (pintype "passive"))
    )
    (net (code "26") (name "/RXP25") (class "Default")
      (node (ref "C80") (pin "1") (pinfunction "1_1") (pintype "passive"))
      (node (ref "J6") (pin "6") (pinfunction "6_6") (pintype "passive"))
      (node (ref "R56") (pin "2") (pinfunction "2_2") (pintype "passive"))
    )
    (net (code "27") (name "/RXP26") (class "Default")
      (node (ref "C96") (pin "1") (pinfunction "1_1") (pintype "passive"))
      (node (ref "J6") (pin "4") (pinfunction "4_4") (pintype "passive"))
      (node (ref "R82") (pin "2") (pinfunction "2_2") (pintype "passive"))
    )
    (net (code "28") (name "/RXP27") (class "Default")
      (node (ref "C178") (pin "1") (pinfunction "1_1") (pintype "passive"))
      (node (ref "J5") (pin "18") (pinfunction "18_18") (pintype "passive"))
      (node (ref "R93") (pin "2") (pinfunction "2_2") (pintype "passive"))
    )
    (net (code "29") (name "/RXP28") (class "Default")
      (node (ref "C194") (pin "1") (pinfunction "1_1") (pintype "passive"))
      (node (ref "J5") (pin "16") (pinfunction "16_16") (pintype "passive"))
      (node (ref "R238") (pin "2") (pinfunction "2_2") (pintype "passive"))
    )
    (net (code "30") (name "/RXP29") (class "Default")
      (node (ref "C81") (pin "1") (pinfunction "1_1") (pintype "passive"))
      (node (ref "J6") (pin "11") (pinfunction "11_11") (pintype "passive"))
      (node (ref "R57") (pin "2") (pinfunction "2_2") (pintype "passive"))
      (node (ref "TP73") (pin "1") (pintype "passive"))
    )
    (net (code "31") (name "/RXP30") (class "Default")
      (node (ref "C97") (pin "1") (pinfunction "1_1") (pintype "passive"))
      (node (ref "J6") (pin "9") (pinfunction "9_9") (pintype "passive"))
      (node (ref "R83") (pin "2") (pinfunction "2_2") (pintype "passive"))
      (node (ref "TP75") (pin "1") (pintype "passive"))
    )
    (net (code "32") (name "/RXP31") (class "Default")
      (node (ref "C84") (pin "1") (pinfunction "1_1") (pintype "passive"))
      (node (ref "J6") (pin "5") (pinfunction "5_5") (pintype "passive"))
      (node (ref "R60") (pin "2") (pinfunction "2_2") (pintype "passive"))
      (node (ref "TP74") (pin "1") (pintype "passive"))
    )
    (net (code "33") (name "/RXP32") (class "Default")
      (node (ref "C175") (pin "1") (pinfunction "1_1") (pintype "passive"))
      (node (ref "J6") (pin "3") (pinfunction "3_3") (pintype "passive"))
      (node (ref "R87") (pin "2") (pinfunction "2_2") (pintype "passive"))
      (node (ref "TP76") (pin "1") (pintype "passive"))
    )
    (net (code "34") (name "/RXP33") (class "Default")
      (node (ref "C191") (pin "1") (pinfunction "1_1") (pintype "passive"))
      (node (ref "J5") (pin "34") (pinfunction "34_34") (pintype "passive"))
      (node (ref "R159") (pin "2") (pinfunction "2_2") (pintype "passive"))
    )
    (net (code "35") (name "/RXP34") (class "Default")
      (node (ref "C213") (pin "1") (pinfunction "1_1") (pintype "passive"))
      (node (ref "J5") (pin "36") (pinfunction "36_36") (pintype "passive"))
      (node (ref "R289") (pin "2") (pinfunction "2_2") (pintype "passive"))
    )
    (net (code "36") (name "/RXP35") (class "Default")
      (node (ref "C86") (pin "1") (pinfunction "1_1") (pintype "passive"))
      (node (ref "J6") (pin "34") (pinfunction "34_34") (pintype "passive"))
      (node (ref "R63") (pin "2") (pinfunction "2_2") (pintype "passive"))
    )
    (net (code "37") (name "/RXP36") (class "Default")
      (node (ref "C177") (pin "1") (pinfunction "1_1") (pintype "passive"))
      (node (ref "J6") (pin "36") (pinfunction "36_36") (pintype "passive"))
      (node (ref "R90") (pin "2") (pinfunction "2_2") (pintype "passive"))
    )
    (net (code "38") (name "/RXP37") (class "Default")
      (node (ref "C82") (pin "1") (pinfunction "1_1") (pintype "passive"))
      (node (ref "J5") (pin "45") (pinfunction "45_45") (pintype "passive"))
      (node (ref "R58") (pin "2") (pinfunction "2_2") (pintype "passive"))
      (node (ref "TP109") (pin "1") (pintype "passive"))
    )
    (net (code "39") (name "/RXP38") (class "Default")
      (node (ref "C98") (pin "1") (pinfunction "1_1") (pintype "passive"))
      (node (ref "J5") (pin "47") (pinfunction "47_47") (pintype "passive"))
      (node (ref "R84") (pin "2") (pinfunction "2_2") (pintype "passive"))
      (node (ref "TP112") (pin "1") (pintype "passive"))
    )
    (net (code "40") (name "/RXP39") (class "Default")
      (node (ref "C190") (pin "1") (pinfunction "1_1") (pintype "passive"))
      (node (ref "J5") (pin "29") (pinfunction "29_29") (pintype "passive"))
      (node (ref "R121") (pin "2") (pinfunction "2_2") (pintype "passive"))
      (node (ref "TP110") (pin "1") (pintype "passive"))
    )
    (net (code "41") (name "/RXP40") (class "Default")
      (node (ref "C207") (pin "1") (pinfunction "1_1") (pintype "passive"))
      (node (ref "J5") (pin "27") (pinfunction "27_27") (pintype "passive"))
      (node (ref "R288") (pin "2") (pinfunction "2_2") (pintype "passive"))
      (node (ref "TP113") (pin "1") (pintype "passive"))
    )
    (net (code "42") (name "/RXP41") (class "Default")
      (node (ref "C193") (pin "1") (pinfunction "1_1") (pintype "passive"))
      (node (ref "J5") (pin "39") (pinfunction "39_39") (pintype "passive"))
      (node (ref "R237") (pin "2") (pinfunction "2_2") (pintype "passive"))
      (node (ref "TP111") (pin "1") (pintype "passive"))
    )
    (net (code "43") (name "/RXP42") (class "Default")
      (node (ref "C215") (pin "1") (pinfunction "1_1") (pintype "passive"))
      (node (ref "J5") (pin "41") (pinfunction "41_41") (pintype "passive"))
      (node (ref "R291") (pin "2") (pinfunction "2_2") (pintype "passive"))
      (node (ref "TP114") (pin "1") (pintype "passive"))
    )
    (net (code "44") (name "/RXP43") (class "Default")
      (node (ref "C76") (pin "1") (pinfunction "1_1") (pintype "passive"))
      (node (ref "J6") (pin "45") (pinfunction "45_45") (pintype "passive"))
      (node (ref "R51") (pin "2") (pinfunction "2_2") (pintype "passive"))
      (node (ref "TP77") (pin "1") (pintype "passive"))
    )
    (net (code "45") (name "/RXP44") (class "Default")
      (node (ref "C92") (pin "1") (pinfunction "1_1") (pintype "passive"))
      (node (ref "J6") (pin "47") (pinfunction "47_47") (pintype "passive"))
      (node (ref "R75") (pin "2") (pinfunction "2_2") (pintype "passive"))
      (node (ref "TP81") (pin "1") (pintype "passive"))
    )
    (net (code "46") (name "/RXP45") (class "Default")
      (node (ref "C75") (pin "1") (pinfunction "1_1") (pintype "passive"))
      (node (ref "J6") (pin "29") (pinfunction "29_29") (pintype "passive"))
      (node (ref "R50") (pin "2") (pinfunction "2_2") (pintype "passive"))
      (node (ref "TP78") (pin "1") (pintype "passive"))
    )
    (net (code "47") (name "/RXP46") (class "Default")
      (node (ref "C91") (pin "1") (pinfunction "1_1") (pintype "passive"))
      (node (ref "J6") (pin "27") (pinfunction "27_27") (pintype "passive"))
      (node (ref "R71") (pin "2") (pinfunction "2_2") (pintype "passive"))
      (node (ref "TP82") (pin "1") (pintype "passive"))
    )
    (net (code "48") (name "/RXP47") (class "Default")
      (node (ref "C182") (pin "1") (pinfunction "1_1") (pintype "passive"))
      (node (ref "J6") (pin "28") (pinfunction "28_28") (pintype "passive"))
      (node (ref "R97") (pin "2") (pinfunction "2_2") (pintype "passive"))
    )
    (net (code "49") (name "/RXP48") (class "Default")
      (node (ref "C198") (pin "1") (pinfunction "1_1") (pintype "passive"))
      (node (ref "J6") (pin "30") (pinfunction "30_30") (pintype "passive"))
      (node (ref "R257") (pin "2") (pinfunction "2_2") (pintype "passive"))
    )
    (net (code "50") (name "/RXP49") (class "Default")
      (node (ref "C83") (pin "1") (pinfunction "1_1") (pintype "passive"))
      (node (ref "J5") (pin "30") (pinfunction "30_30") (pintype "passive"))
      (node (ref "R59") (pin "2") (pinfunction "2_2") (pintype "passive"))
    )
    (net (code "51") (name "/RXP50") (class "Default")
      (node (ref "C174") (pin "1") (pinfunction "1_1") (pintype "passive"))
      (node (ref "J5") (pin "28") (pinfunction "28_28") (pintype "passive"))
      (node (ref "R85") (pin "2") (pinfunction "2_2") (pintype "passive"))
    )
    (net (code "52") (name "/RXP51") (class "Default")
      (node (ref "C184") (pin "1") (pinfunction "1_1") (pintype "passive"))
      (node (ref "J5") (pin "40") (pinfunction "40_40") (pintype "passive"))
      (node (ref "R99") (pin "2") (pinfunction "2_2") (pintype "passive"))
    )
    (net (code "53") (name "/RXP52") (class "Default")
      (node (ref "C200") (pin "1") (pinfunction "1_1") (pintype "passive"))
      (node (ref "J5") (pin "42") (pinfunction "42_42") (pintype "passive"))
      (node (ref "R259") (pin "2") (pinfunction "2_2") (pintype "passive"))
    )
    (net (code "54") (name "/RXP53") (class "Default")
      (node (ref "C2") (pin "1") (pinfunction "1_1") (pintype "passive"))
      (node (ref "J6") (pin "39") (pinfunction "39_39") (pintype "passive"))
      (node (ref "R328") (pin "2") (pinfunction "2_2") (pintype "passive"))
      (node (ref "TP79") (pin "1") (pintype "passive"))
    )
    (net (code "55") (name "/RXP54") (class "Default")
      (node (ref "C5") (pin "1") (pinfunction "1_1") (pintype "passive"))
      (node (ref "J6") (pin "41") (pinfunction "41_41") (pintype "passive"))
      (node (ref "R343") (pin "2") (pinfunction "2_2") (pintype "passive"))
      (node (ref "TP83") (pin "1") (pintype "passive"))
    )
    (net (code "56") (name "/RXP55") (class "Default")
      (node (ref "C183") (pin "1") (pinfunction "1_1") (pintype "passive"))
      (node (ref "J6") (pin "35") (pinfunction "35_35") (pintype "passive"))
      (node (ref "R98") (pin "2") (pinfunction "2_2") (pintype "passive"))
      (node (ref "TP80") (pin "1") (pintype "passive"))
    )
    (net (code "57") (name "/RXP56") (class "Default")
      (node (ref "C199") (pin "1") (pinfunction "1_1") (pintype "passive"))
      (node (ref "J6") (pin "33") (pinfunction "33_33") (pintype "passive"))
      (node (ref "R258") (pin "2") (pinfunction "2_2") (pintype "passive"))
      (node (ref "TP84") (pin "1") (pintype "passive"))
    )
    (net (code "58") (name "/RXP57") (class "Default")
      (node (ref "C6") (pin "1") (pinfunction "1_1") (pintype "passive"))
      (node (ref "J5") (pin "46") (pinfunction "46_46") (pintype "passive"))
      (node (ref "R349") (pin "2") (pinfunction "2_2") (pintype "passive"))
    )
    (net (code "59") (name "/RXP58") (class "Default")
      (node (ref "C22") (pin "1") (pinfunction "1_1") (pintype "passive"))
      (node (ref "J5") (pin "48") (pinfunction "48_48") (pintype "passive"))
      (node (ref "R359") (pin "2") (pinfunction "2_2") (pintype "passive"))
    )
    (net (code "60") (name "/RXP59") (class "Default")
      (node (ref "C185") (pin "1") (pinfunction "1_1") (pintype "passive"))
      (node (ref "J5") (pin "33") (pinfunction "33_33") (pintype "passive"))
      (node (ref "R101") (pin "2") (pinfunction "2_2") (pintype "passive"))
      (node (ref "TP115") (pin "1") (pintype "passive"))
    )
    (net (code "61") (name "/RXP60") (class "Default")
      (node (ref "C201") (pin "1") (pinfunction "1_1") (pintype "passive"))
      (node (ref "J5") (pin "35") (pinfunction "35_35") (pintype "passive"))
      (node (ref "R260") (pin "2") (pinfunction "2_2") (pintype "passive"))
      (node (ref "TP116") (pin "1") (pintype "passive"))
    )
    (net (code "62") (name "/RXP61") (class "Default")
      (node (ref "C77") (pin "1") (pinfunction "1_1") (pintype "passive"))
      (node (ref "J6") (pin "46") (pinfunction "46_46") (pintype "passive"))
      (node (ref "R53") (pin "2") (pinfunction "2_2") (pintype "passive"))
    )
    (net (code "63") (name "/RXP62") (class "Default")
      (node (ref "C93") (pin "1") (pinfunction "1_1") (pintype "passive"))
      (node (ref "J6") (pin "48") (pinfunction "48_48") (pintype "passive"))
      (node (ref "R76") (pin "2") (pinfunction "2_2") (pintype "passive"))
    )
    (net (code "64") (name "/RXP63") (class "Default")
      (node (ref "C73") (pin "1") (pinfunction "1_1") (pintype "passive"))
      (node (ref "J6") (pin "40") (pinfunction "40_40") (pintype "passive"))
      (node (ref "R48") (pin "2") (pinfunction "2_2") (pintype "passive"))
    )
    (net (code "65") (name "/RXP64") (class "Default")
      (node (ref "C89") (pin "1") (pinfunction "1_1") (pintype "passive"))
      (node (ref "J6") (pin "42") (pinfunction "42_42") (pintype "passive"))
      (node (ref "R69") (pin "2") (pinfunction "2_2") (pintype "passive"))
    )
    (net (code "66") (name "GND") (class "Default")
      (node (ref "C174") (pin "2") (pinfunction "2_2") (pintype "passive"))
      (node (ref "C175") (pin "2") (pinfunction "2_2") (pintype "passive"))
      (node (ref "C177") (pin "2") (pinfunction "2_2") (pintype "passive"))
      (node (ref "C178") (pin "2") (pinfunction "2_2") (pintype "passive"))
      (node (ref "C179") (pin "2") (pinfunction "2_2") (pintype "passive"))
      (node (ref "C180") (pin "2") (pinfunction "2_2") (pintype "passive"))
      (node (ref "C181") (pin "2") (pinfunction "2_2") (pintype "passive"))
      (node (ref "C182") (pin "2") (pinfunction "2_2") (pintype "passive"))
      (node (ref "C183") (pin "2") (pinfunction "2_2") (pintype "passive"))
      (node (ref "C184") (pin "2") (pinfunction "2_2") (pintype "passive"))
      (node (ref "C185") (pin "2") (pinfunction "2_2") (pintype "passive"))
      (node (ref "C186") (pin "2") (pinfunction "2_2") (pintype "passive"))
      (node (ref "C187") (pin "2") (pinfunction "2_2") (pintype "passive"))
      (node (ref "C188") (pin "2") (pinfunction "2_2") (pintype "passive"))
      (node (ref "C189") (pin "2") (pinfunction "2_2") (pintype "passive"))
      (node (ref "C190") (pin "2") (pinfunction "2_2") (pintype "passive"))
      (node (ref "C191") (pin "2") (pinfunction "2_2") (pintype "passive"))
      (node (ref "C193") (pin "2") (pinfunction "2_2") (pintype "passive"))
      (node (ref "C194") (pin "2") (pinfunction "2_2") (pintype "passive"))
      (node (ref "C195") (pin "2") (pinfunction "2_2") (pintype "passive"))
      (node (ref "C196") (pin "2") (pinfunction "2_2") (pintype "passive"))
      (node (ref "C197") (pin "2") (pinfunction "2_2") (pintype "passive"))
      (node (ref "C198") (pin "2") (pinfunction "2_2") (pintype "passive"))
      (node (ref "C199") (pin "2") (pinfunction "2_2") (pintype "passive"))
      (node (ref "C2") (pin "2") (pinfunction "2_2") (pintype "passive"))
      (node (ref "C200") (pin "2") (pinfunction "2_2") (pintype "passive"))
      (node (ref "C201") (pin "2") (pinfunction "2_2") (pintype "passive"))
      (node (ref "C202") (pin "2") (pinfunction "2_2") (pintype "passive"))
      (node (ref "C203") (pin "2") (pinfunction "2_2") (pintype "passive"))
      (node (ref "C204") (pin "2") (pinfunction "2_2") (pintype "passive"))
      (node (ref "C205") (pin "2") (pinfunction "2_2") (pintype "passive"))
      (node (ref "C207") (pin "2") (pinfunction "2_2") (pintype "passive"))
      (node (ref "C213") (pin "2") (pinfunction "2_2") (pintype "passive"))
      (node (ref "C215") (pin "2") (pinfunction "2_2") (pintype "passive"))
      (node (ref "C22") (pin "2") (pinfunction "2_2") (pintype "passive"))
      (node (ref "C5") (pin "2") (pinfunction "2_2") (pintype "passive"))
      (node (ref "C6") (pin "2") (pinfunction "2_2") (pintype "passive"))
      (node (ref "C71") (pin "2") (pinfunction "2_2") (pintype "passive"))
      (node (ref "C72") (pin "2") (pinfunction "2_2") (pintype "passive"))
      (node (ref "C73") (pin "2") (pinfunction "2_2") (pintype "passive"))
      (node (ref "C74") (pin "2") (pinfunction "2_2") (pintype "passive"))
      (node (ref "C75") (pin "2") (pinfunction "2_2") (pintype "passive"))
      (node (ref "C76") (pin "2") (pinfunction "2_2") (pintype "passive"))
      (node (ref "C77") (pin "2") (pinfunction "2_2") (pintype "passive"))
      (node (ref "C78") (pin "2") (pinfunction "2_2") (pintype "passive"))
      (node (ref "C79") (pin "2") (pinfunction "2_2") (pintype "passive"))
      (node (ref "C80") (pin "2") (pinfunction "2_2") (pintype "passive"))
      (node (ref "C81") (pin "2") (pinfunction "2_2") (pintype "passive"))
      (node (ref "C82") (pin "2") (pinfunction "2_2") (pintype "passive"))
      (node (ref "C83") (pin "2") (pinfunction "2_2") (pintype "passive"))
      (node (ref "C84") (pin "2") (pinfunction "2_2") (pintype "passive"))
      (node (ref "C86") (pin "2") (pinfunction "2_2") (pintype "passive"))
      (node (ref "C87") (pin "2") (pinfunction "2_2") (pintype "passive"))
      (node (ref "C88") (pin "2") (pinfunction "2_2") (pintype "passive"))
      (node (ref "C89") (pin "2") (pinfunction "2_2") (pintype "passive"))
      (node (ref "C90") (pin "2") (pinfunction "2_2") (pintype "passive"))
      (node (ref "C91") (pin "2") (pinfunction "2_2") (pintype "passive"))
      (node (ref "C92") (pin "2") (pinfunction "2_2") (pintype "passive"))
      (node (ref "C93") (pin "2") (pinfunction "2_2") (pintype "passive"))
      (node (ref "C94") (pin "2") (pinfunction "2_2") (pintype "passive"))
      (node (ref "C95") (pin "2") (pinfunction "2_2") (pintype "passive"))
      (node (ref "C96") (pin "2") (pinfunction "2_2") (pintype "passive"))
      (node (ref "C97") (pin "2") (pinfunction "2_2") (pintype "passive"))
      (node (ref "C98") (pin "2") (pinfunction "2_2") (pintype "passive"))
      (node (ref "J5") (pin "1") (pinfunction "1_1") (pintype "passive"))
      (node (ref "J5") (pin "13") (pinfunction "13_13") (pintype "passive"))
      (node (ref "J5") (pin "14") (pinfunction "14_14") (pintype "passive"))
      (node (ref "J5") (pin "19") (pinfunction "19_19") (pintype "passive"))
      (node (ref "J5") (pin "2") (pinfunction "2_2") (pintype "passive"))
      (node (ref "J5") (pin "20") (pinfunction "20_20") (pintype "passive"))
      (node (ref "J5") (pin "25") (pinfunction "25_25") (pintype "passive"))
      (node (ref "J5") (pin "26") (pinfunction "26_26") (pintype "passive"))
      (node (ref "J5") (pin "31") (pinfunction "31_31") (pintype "passive"))
      (node (ref "J5") (pin "32") (pinfunction "32_32") (pintype "passive"))
      (node (ref "J5") (pin "37") (pinfunction "37_37") (pintype "passive"))
      (node (ref "J5") (pin "38") (pinfunction "38_38") (pintype "passive"))
      (node (ref "J5") (pin "43") (pinfunction "43_43") (pintype "passive"))
      (node (ref "J5") (pin "44") (pinfunction "44_44") (pintype "passive"))
      (node (ref "J5") (pin "49") (pinfunction "49_49") (pintype "passive"))
      (node (ref "J5") (pin "50") (pinfunction "50_50") (pintype "passive"))
      (node (ref "J5") (pin "7") (pinfunction "7_7") (pintype "passive"))
      (node (ref "J5") (pin "8") (pinfunction "8_8") (pintype "passive"))
      (node (ref "J6") (pin "1") (pinfunction "1_1") (pintype "passive"))
      (node (ref "J6") (pin "13") (pinfunction "13_13") (pintype "passive"))
      (node (ref "J6") (pin "14") (pinfunction "14_14") (pintype "passive"))
      (node (ref "J6") (pin "19") (pinfunction "19_19") (pintype "passive"))
      (node (ref "J6") (pin "2") (pinfunction "2_2") (pintype "passive"))
      (node (ref "J6") (pin "20") (pinfunction "20_20") (pintype "passive"))
      (node (ref "J6") (pin "25") (pinfunction "25_25") (pintype "passive"))
      (node (ref "J6") (pin "26") (pinfunction "26_26") (pintype "passive"))
      (node (ref "J6") (pin "31") (pinfunction "31_31") (pintype "passive"))
      (node (ref "J6") (pin "32") (pinfunction "32_32") (pintype "passive"))
      (node (ref "J6") (pin "37") (pinfunction "37_37") (pintype "passive"))
      (node (ref "J6") (pin "38") (pinfunction "38_38") (pintype "passive"))
      (node (ref "J6") (pin "43") (pinfunction "43_43") (pintype "passive"))
      (node (ref "J6") (pin "44") (pinfunction "44_44") (pintype "passive"))
      (node (ref "J6") (pin "49") (pinfunction "49_49") (pintype "passive"))
      (node (ref "J6") (pin "50") (pinfunction "50_50") (pintype "passive"))
      (node (ref "J6") (pin "7") (pinfunction "7_7") (pintype "passive"))
      (node (ref "J6") (pin "8") (pinfunction "8_8") (pintype "passive"))
      (node (ref "R101") (pin "1") (pinfunction "1_1") (pintype "passive"))
      (node (ref "R102") (pin "1") (pinfunction "1_1") (pintype "passive"))
      (node (ref "R106") (pin "1") (pinfunction "1_1") (pintype "passive"))
      (node (ref "R107") (pin "1") (pinfunction "1_1") (pintype "passive"))
      (node (ref "R117") (pin "1") (pinfunction "1_1") (pintype "passive"))
      (node (ref "R121") (pin "1") (pinfunction "1_1") (pintype "passive"))
      (node (ref "R159") (pin "1") (pinfunction "1_1") (pintype "passive"))
      (node (ref "R237") (pin "1") (pinfunction "1_1") (pintype "passive"))
      (node (ref "R238") (pin "1") (pinfunction "1_1") (pintype "passive"))
      (node (ref "R239") (pin "1") (pinfunction "1_1") (pintype "passive"))
      (node (ref "R255") (pin "1") (pinfunction "1_1") (pintype "passive"))
      (node (ref "R256") (pin "1") (pinfunction "1_1") (pintype "passive"))
      (node (ref "R257") (pin "1") (pinfunction "1_1") (pintype "passive"))
      (node (ref "R258") (pin "1") (pinfunction "1_1") (pintype "passive"))
      (node (ref "R259") (pin "1") (pinfunction "1_1") (pintype "passive"))
      (node (ref "R260") (pin "1") (pinfunction "1_1") (pintype "passive"))
      (node (ref "R261") (pin "1") (pinfunction "1_1") (pintype "passive"))
      (node (ref "R281") (pin "1") (pinfunction "1_1") (pintype "passive"))
      (node (ref "R282") (pin "1") (pinfunction "1_1") (pintype "passive"))
      (node (ref "R287") (pin "1") (pinfunction "1_1") (pintype "passive"))
      (node (ref "R288") (pin "1") (pinfunction "1_1") (pintype "passive"))
      (node (ref "R289") (pin "1") (pinfunction "1_1") (pintype "passive"))
      (node (ref "R291") (pin "1") (pinfunction "1_1") (pintype "passive"))
      (node (ref "R328") (pin "1") (pinfunction "1_1") (pintype "passive"))
      (node (ref "R343") (pin "1") (pinfunction "1_1") (pintype "passive"))
      (node (ref "R349") (pin "1") (pinfunction "1_1") (pintype "passive"))
      (node (ref "R359") (pin "1") (pinfunction "1_1") (pintype "passive"))
      (node (ref "R46") (pin "1") (pinfunction "1_1") (pintype "passive"))
      (node (ref "R47") (pin "1") (pinfunction "1_1") (pintype "passive"))
      (node (ref "R48") (pin "1") (pinfunction "1_1") (pintype "passive"))
      (node (ref "R49") (pin "1") (pinfunction "1_1") (pintype "passive"))
      (node (ref "R50") (pin "1") (pinfunction "1_1") (pintype "passive"))
      (node (ref "R51") (pin "1") (pinfunction "1_1") (pintype "passive"))
      (node (ref "R53") (pin "1") (pinfunction "1_1") (pintype "passive"))
      (node (ref "R54") (pin "1") (pinfunction "1_1") (pintype "passive"))
      (node (ref "R55") (pin "1") (pinfunction "1_1") (pintype "passive"))
      (node (ref "R56") (pin "1") (pinfunction "1_1") (pintype "passive"))
      (node (ref "R57") (pin "1") (pinfunction "1_1") (pintype "passive"))
      (node (ref "R58") (pin "1") (pinfunction "1_1") (pintype "passive"))
      (node (ref "R59") (pin "1") (pinfunction "1_1") (pintype "passive"))
      (node (ref "R60") (pin "1") (pinfunction "1_1") (pintype "passive"))
      (node (ref "R63") (pin "1") (pinfunction "1_1") (pintype "passive"))
      (node (ref "R64") (pin "1") (pinfunction "1_1") (pintype "passive"))
      (node (ref "R68") (pin "1") (pinfunction "1_1") (pintype "passive"))
      (node (ref "R69") (pin "1") (pinfunction "1_1") (pintype "passive"))
      (node (ref "R70") (pin "1") (pinfunction "1_1") (pintype "passive"))
      (node (ref "R71") (pin "1") (pinfunction "1_1") (pintype "passive"))
      (node (ref "R75") (pin "1") (pinfunction "1_1") (pintype "passive"))
      (node (ref "R76") (pin "1") (pinfunction "1_1") (pintype "passive"))
      (node (ref "R80") (pin "1") (pinfunction "1_1") (pintype "passive"))
      (node (ref "R81") (pin "1") (pinfunction "1_1") (pintype "passive"))
      (node (ref "R82") (pin "1") (pinfunction "1_1") (pintype "passive"))
      (node (ref "R83") (pin "1") (pinfunction "1_1") (pintype "passive"))
      (node (ref "R84") (pin "1") (pinfunction "1_1") (pintype "passive"))
      (node (ref "R85") (pin "1") (pinfunction "1_1") (pintype "passive"))
      (node (ref "R87") (pin "1") (pinfunction "1_1") (pintype "passive"))
      (node (ref "R90") (pin "1") (pinfunction "1_1") (pintype "passive"))
      (node (ref "R93") (pin "1") (pinfunction "1_1") (pintype "passive"))
      (node (ref "R94") (pin "1") (pinfunction "1_1") (pintype "passive"))
      (node (ref "R95") (pin "1") (pinfunction "1_1") (pintype "passive"))
      (node (ref "R96") (pin "1") (pinfunction "1_1") (pintype "passive"))
      (node (ref "R97") (pin "1") (pinfunction "1_1") (pintype "passive"))
      (node (ref "R98") (pin "1") (pinfunction "1_1") (pintype "passive"))
      (node (ref "R99") (pin "1") (pinfunction "1_1") (pintype "passive"))
    )
  )
)
